# Main_Board.net
KiCad netlist of a schematic drawn in EAGLE
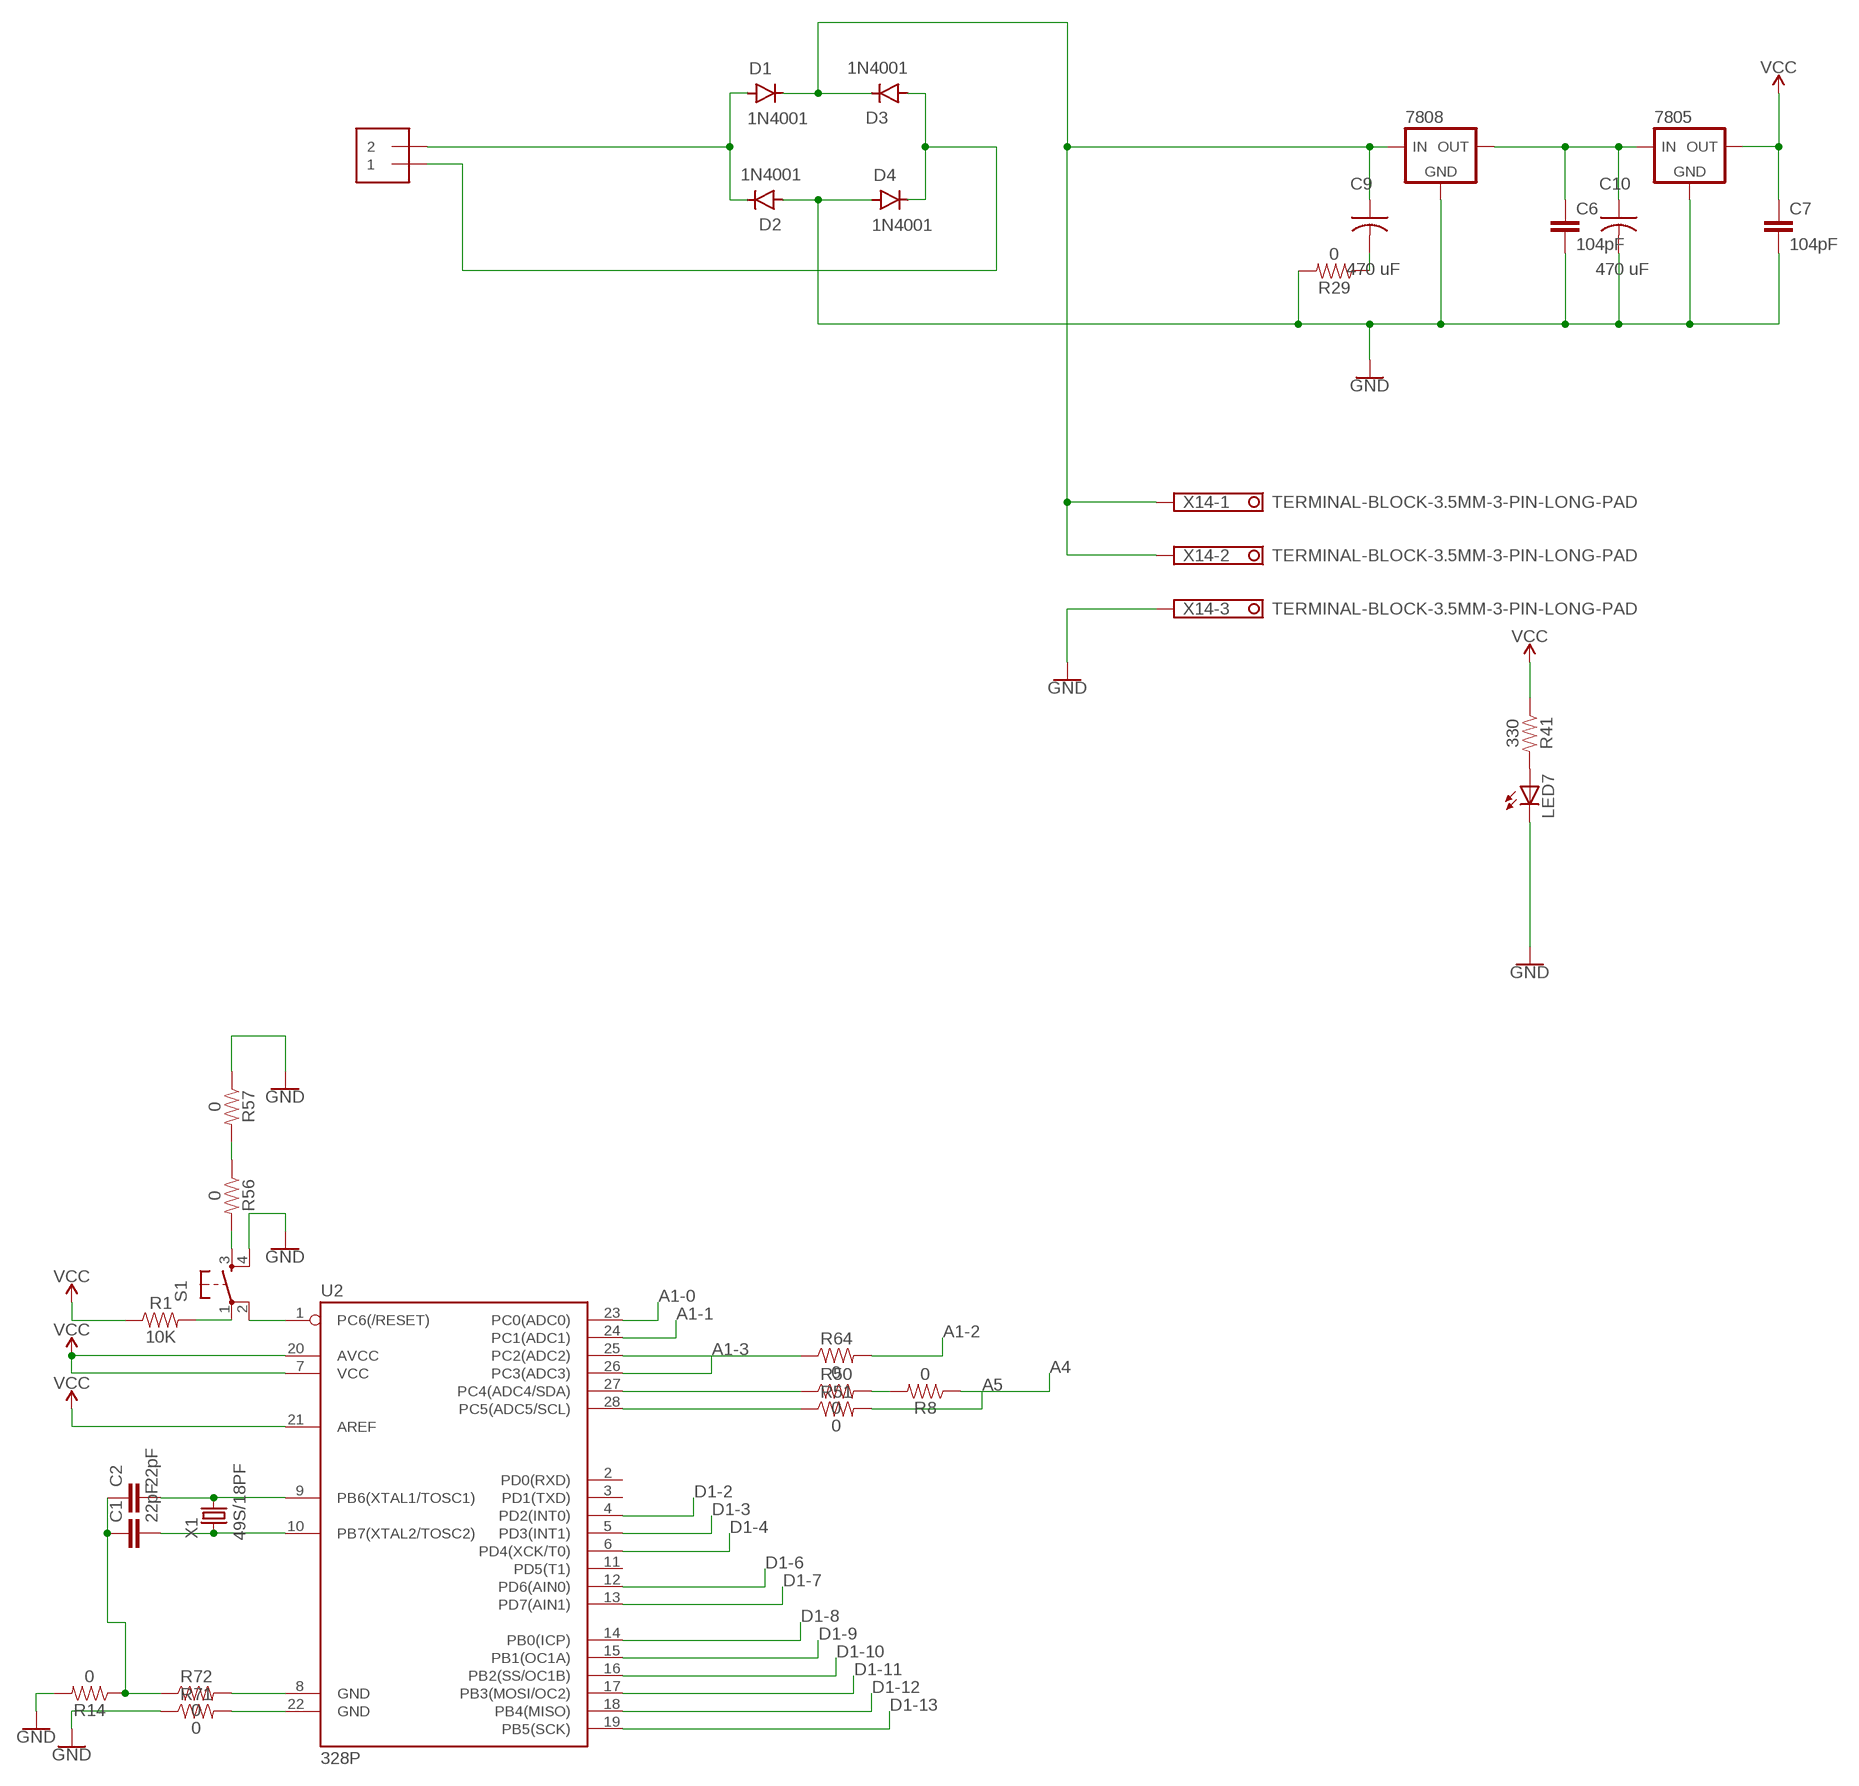
[diagram p0: schematic, sheet 1, part 1 of 3]
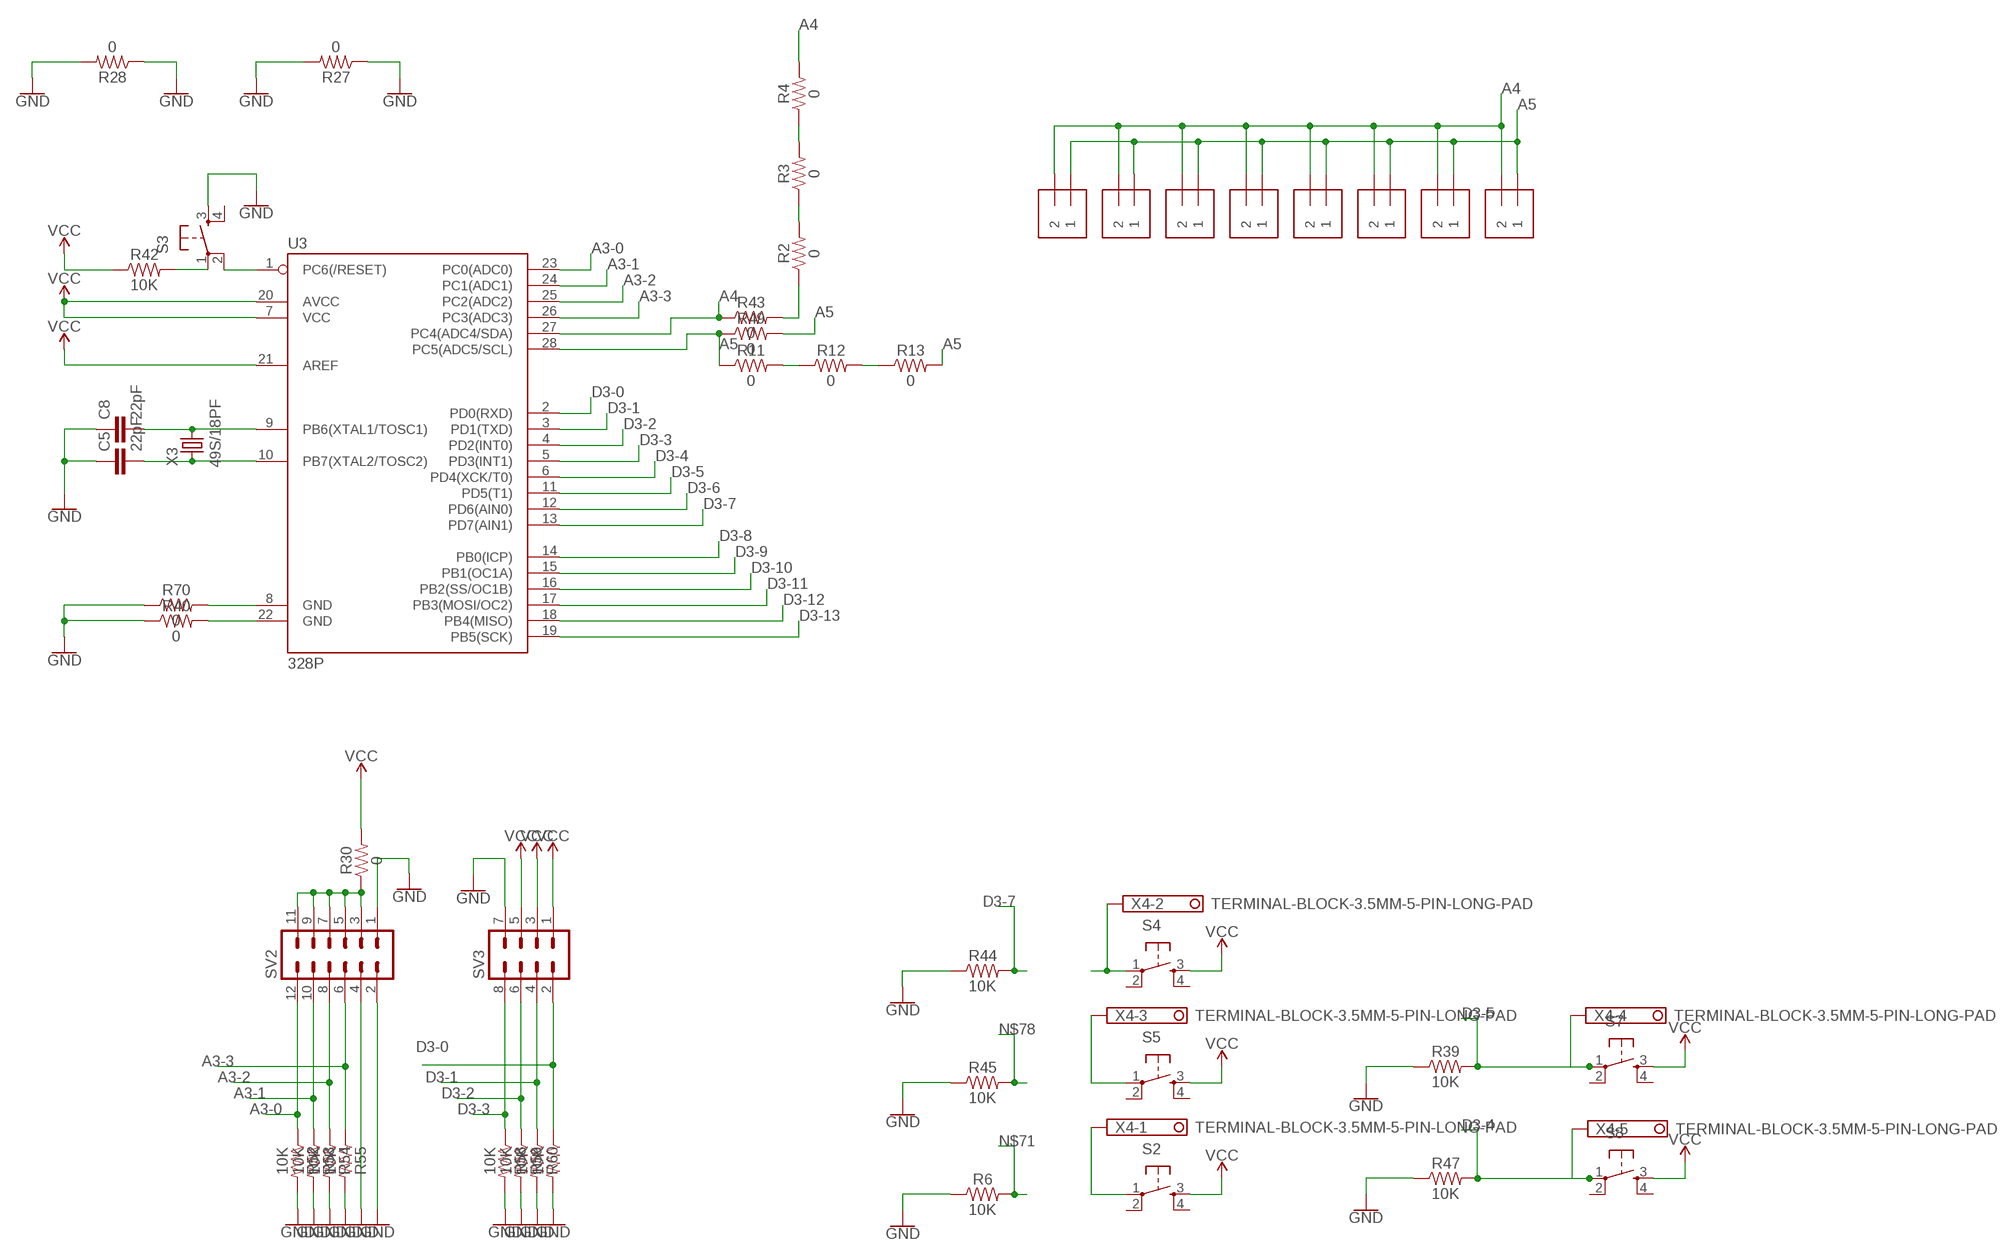
[diagram p1: schematic, sheet 1, part 2 of 3]
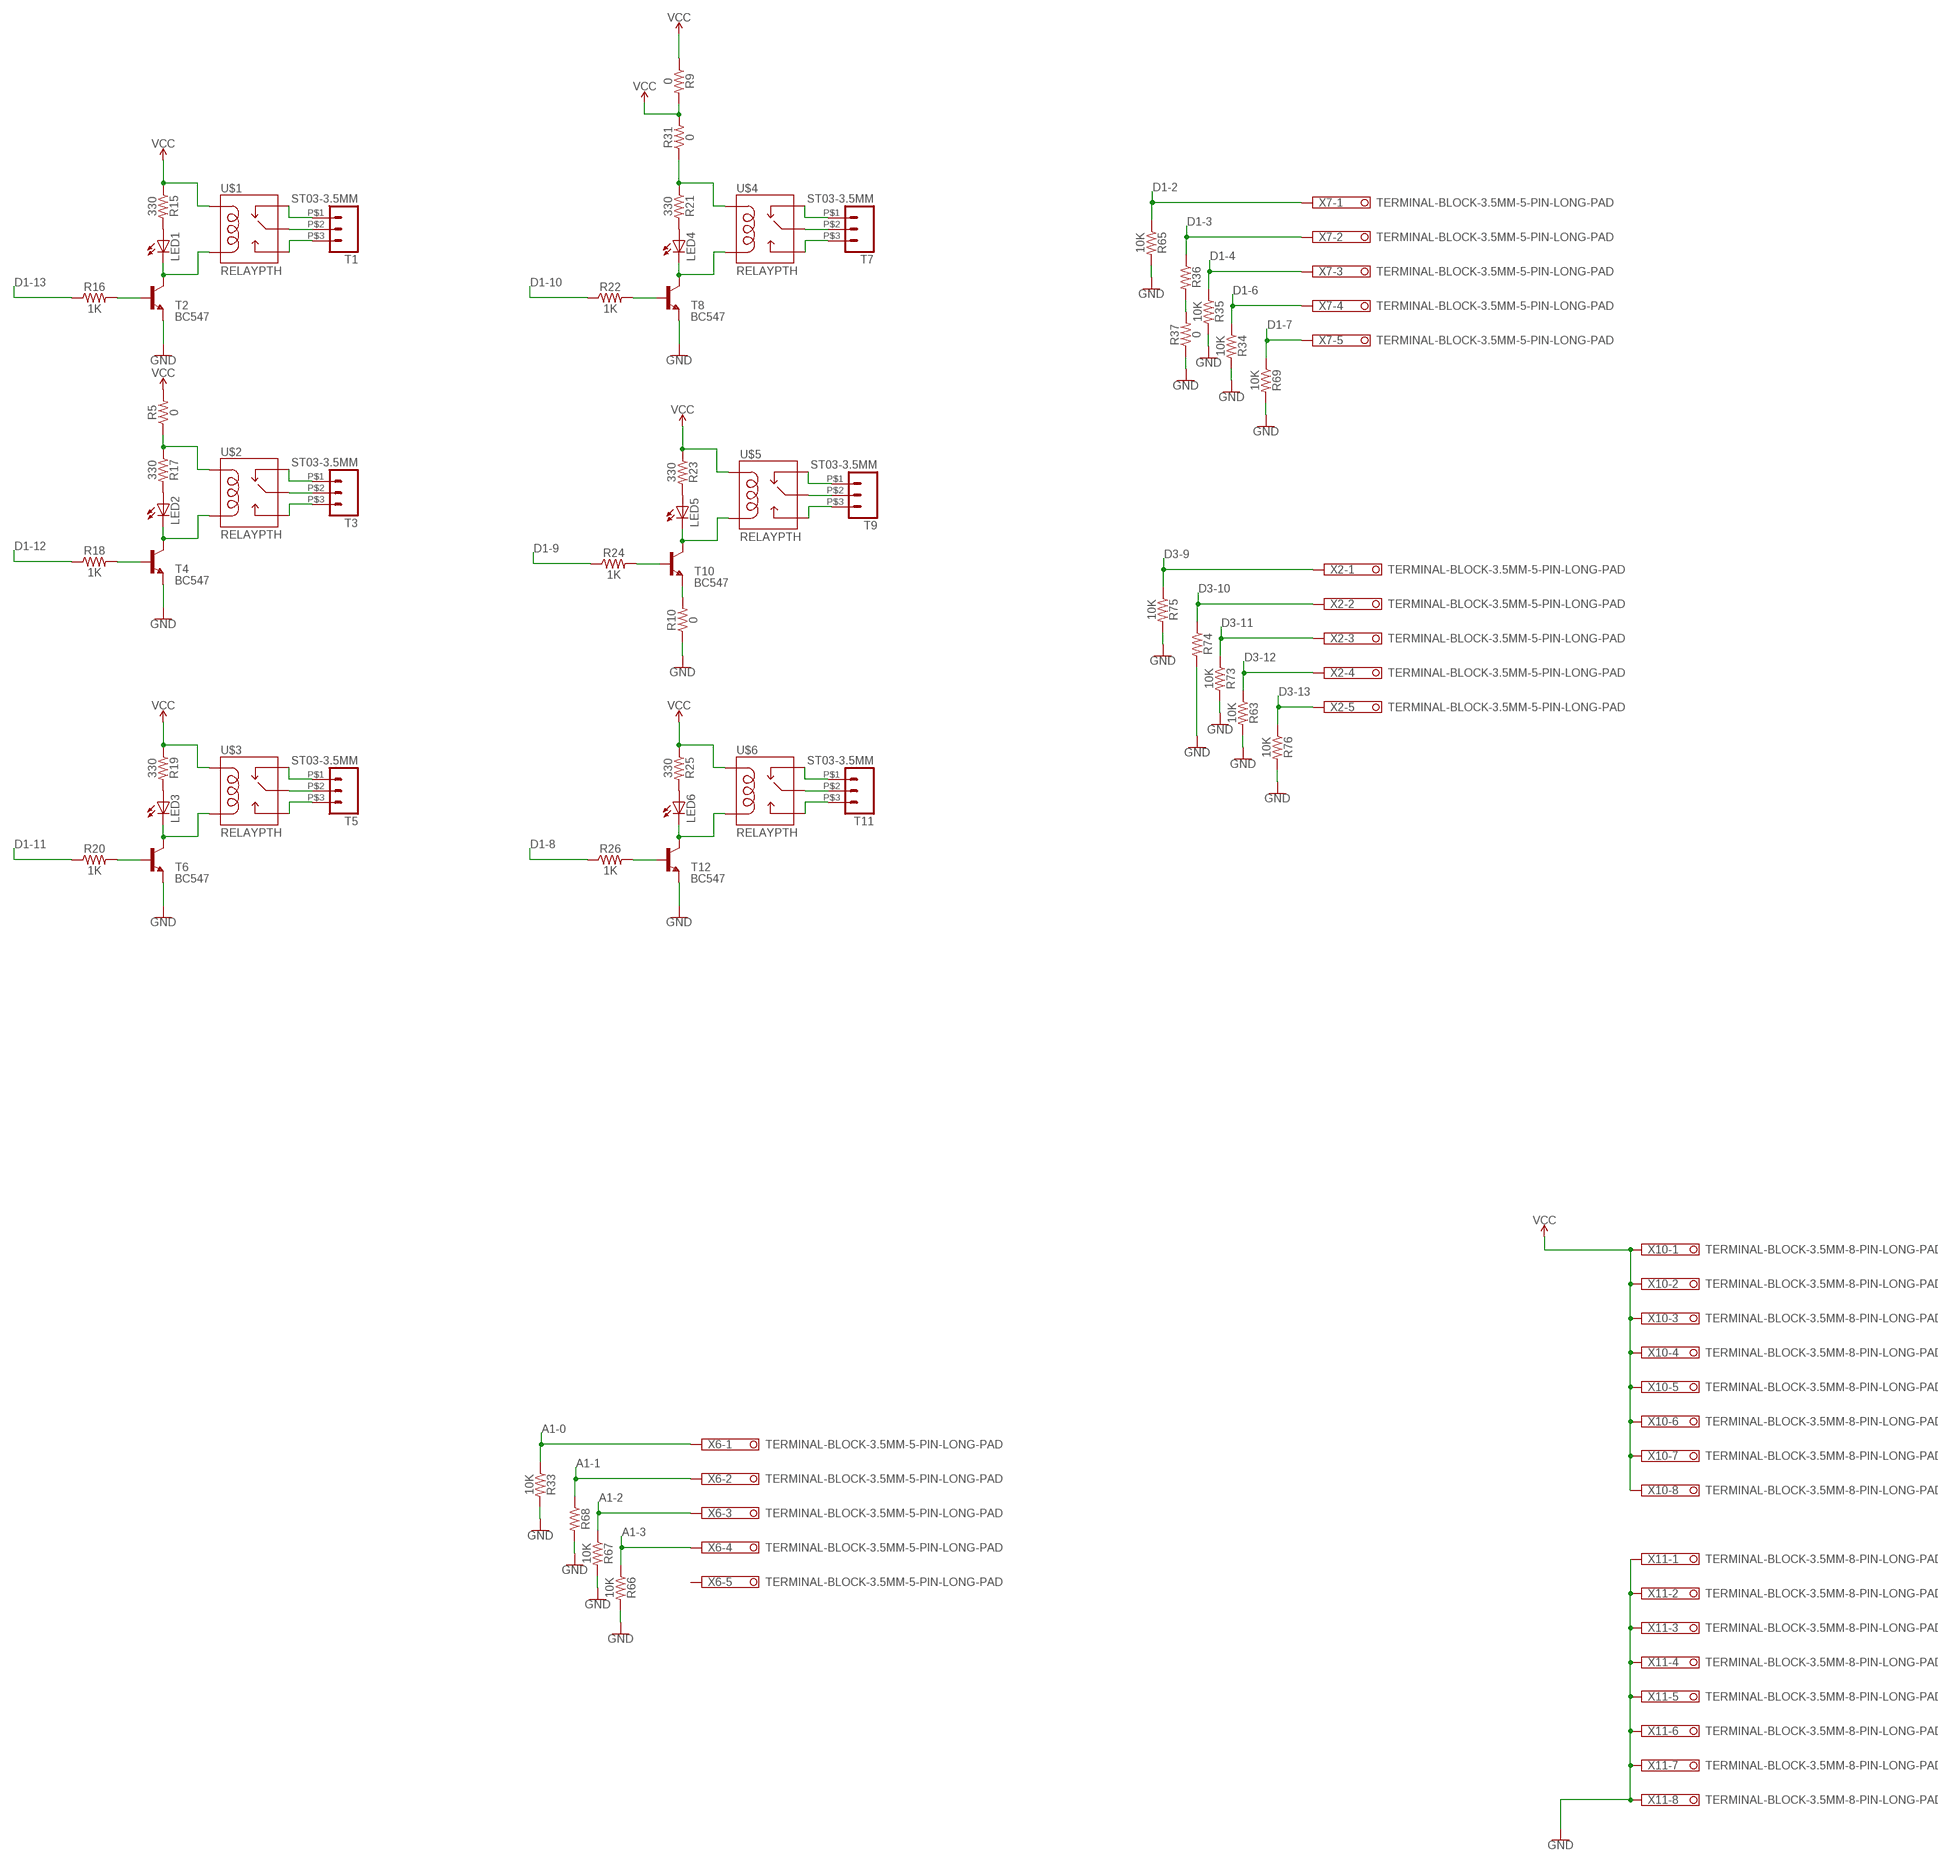
[diagram p2: schematic, sheet 1, part 3 of 3]

(export (version "E")
  (design (tool "Eeschema 10.0.6"))
  (components
    (comp (ref "7805")
      (value "78XX-TO220H-NH")
      (footprint "eagle-import:TO220BH-NH")
      (libsource (lib "eagle-import") (part "78XX-TO220H-NH"))
    )
    (comp (ref "7808")
      (value "78XX-TO220H-NH")
      (footprint "eagle-import:TO220BH-NH")
      (libsource (lib "eagle-import") (part "78XX-TO220H-NH"))
    )
    (comp (ref "C1")
      (value "22pF")
      (footprint "eagle-import:CAP-PTH-2.54")
      (libsource (lib "eagle-import") (part "22PF-PTH-2.54MM-200V-5%"))
    )
    (comp (ref "C2")
      (value "22pF")
      (footprint "eagle-import:CAP-PTH-2.54")
      (libsource (lib "eagle-import") (part "22PF-PTH-2.54MM-200V-5%"))
    )
    (comp (ref "C5")
      (value "22pF")
      (footprint "eagle-import:CAP-PTH-2.54")
      (libsource (lib "eagle-import") (part "22PF-PTH-2.54MM-200V-5%"))
    )
    (comp (ref "C6")
      (value "104pF")
      (footprint "eagle-import:CAP-PTH-2.54")
      (libsource (lib "eagle-import") (part "22PF-PTH-2.54MM-200V-5%"))
    )
    (comp (ref "C7")
      (value "104pF")
      (footprint "eagle-import:CAP-PTH-2.54")
      (libsource (lib "eagle-import") (part "22PF-PTH-2.54MM-200V-5%"))
    )
    (comp (ref "C8")
      (value "22pF")
      (footprint "eagle-import:CAP-PTH-2.54")
      (libsource (lib "eagle-import") (part "22PF-PTH-2.54MM-200V-5%"))
    )
    (comp (ref "C9")
      (value "470 uF")
      (footprint "eagle-import:CAP_RADIAL_5MM")
      (fields
        (field (name "DIGIKEY_PART_NUMBER") "P5156-ND")
        (field (name "MANUFACTURER") "Panasonic Electronic Components")
        (field (name "MPN") "ECA-1EM102")
        (field (name "CREATED_BY") "PCBLayout.com")
      )
      (libsource (lib "eagle-import") (part "ECA-1EM102"))
    )
    (comp (ref "C10")
      (value "470 uF")
      (footprint "eagle-import:CAP_RADIAL_5MM")
      (fields
        (field (name "DIGIKEY_PART_NUMBER") "P5156-ND")
        (field (name "MANUFACTURER") "Panasonic Electronic Components")
        (field (name "MPN") "ECA-1EM102")
        (field (name "CREATED_BY") "PCBLayout.com")
      )
      (libsource (lib "eagle-import") (part "ECA-1EM102"))
    )
    (comp (ref "D1")
      (value "1N4001")
      (footprint "eagle-import:DO-41")
      (fields
        (field (name "DIGIKEY_PART_NUMBER") "1N4004MSCT-ND")
        (field (name "MANUFACTURER") "Micro Commercial Co")
        (field (name "MPN") "1N4004")
        (field (name "CREATED_BY") "PCBLayout.com")
      )
      (libsource (lib "eagle-import") (part "1N4004"))
    )
    (comp (ref "D2")
      (value "1N4001")
      (footprint "eagle-import:DO-41")
      (fields
        (field (name "DIGIKEY_PART_NUMBER") "1N4004MSCT-ND")
        (field (name "MANUFACTURER") "Micro Commercial Co")
        (field (name "MPN") "1N4004")
        (field (name "CREATED_BY") "PCBLayout.com")
      )
      (libsource (lib "eagle-import") (part "1N4004"))
    )
    (comp (ref "D3")
      (value "1N4001")
      (footprint "eagle-import:DO-41")
      (fields
        (field (name "DIGIKEY_PART_NUMBER") "1N4004MSCT-ND")
        (field (name "MANUFACTURER") "Micro Commercial Co")
        (field (name "MPN") "1N4004")
        (field (name "CREATED_BY") "PCBLayout.com")
      )
      (libsource (lib "eagle-import") (part "1N4004"))
    )
    (comp (ref "D4")
      (value "1N4001")
      (footprint "eagle-import:DO-41")
      (fields
        (field (name "DIGIKEY_PART_NUMBER") "1N4004MSCT-ND")
        (field (name "MANUFACTURER") "Micro Commercial Co")
        (field (name "MPN") "1N4004")
        (field (name "CREATED_BY") "PCBLayout.com")
      )
      (libsource (lib "eagle-import") (part "1N4004"))
    )
    (comp (ref "LED1")
      (value "LED5MM")
      (footprint "eagle-import:LED5MM")
      (libsource (lib "eagle-import") (part "LED5MM"))
    )
    (comp (ref "LED2")
      (value "LED5MM")
      (footprint "eagle-import:LED5MM")
      (libsource (lib "eagle-import") (part "LED5MM"))
    )
    (comp (ref "LED3")
      (value "LED5MM")
      (footprint "eagle-import:LED5MM")
      (libsource (lib "eagle-import") (part "LED5MM"))
    )
    (comp (ref "LED4")
      (value "LED5MM")
      (footprint "eagle-import:LED5MM")
      (libsource (lib "eagle-import") (part "LED5MM"))
    )
    (comp (ref "LED5")
      (value "LED5MM")
      (footprint "eagle-import:LED5MM")
      (libsource (lib "eagle-import") (part "LED5MM"))
    )
    (comp (ref "LED6")
      (value "LED5MM")
      (footprint "eagle-import:LED5MM")
      (libsource (lib "eagle-import") (part "LED5MM"))
    )
    (comp (ref "LED7")
      (value "LED5MM")
      (footprint "eagle-import:LED5MM")
      (libsource (lib "eagle-import") (part "LED5MM"))
    )
    (comp (ref "POWER-INPUT")
      (value "1X2-3.5MM")
      (footprint "eagle-import:1X2-3.5MM")
      (libsource (lib "eagle-import") (part "1X2-3.5MM"))
    )
    (comp (ref "POWER-INPUT1")
      (value "1X2-3.5MM")
      (footprint "eagle-import:1X2-3.5MM")
      (libsource (lib "eagle-import") (part "1X2-3.5MM"))
    )
    (comp (ref "POWER-INPUT2")
      (value "1X2-3.5MM")
      (footprint "eagle-import:1X2-3.5MM")
      (libsource (lib "eagle-import") (part "1X2-3.5MM"))
    )
    (comp (ref "POWER-INPUT3")
      (value "1X2-3.5MM")
      (footprint "eagle-import:1X2-3.5MM")
      (libsource (lib "eagle-import") (part "1X2-3.5MM"))
    )
    (comp (ref "POWER-INPUT4")
      (value "1X2-3.5MM")
      (footprint "eagle-import:1X2-3.5MM")
      (libsource (lib "eagle-import") (part "1X2-3.5MM"))
    )
    (comp (ref "POWER-INPUT5")
      (value "1X2-3.5MM")
      (footprint "eagle-import:1X2-3.5MM")
      (libsource (lib "eagle-import") (part "1X2-3.5MM"))
    )
    (comp (ref "POWER-INPUT6")
      (value "1X2-3.5MM")
      (footprint "eagle-import:1X2-3.5MM")
      (libsource (lib "eagle-import") (part "1X2-3.5MM"))
    )
    (comp (ref "POWER-INPUT7")
      (value "1X2-3.5MM")
      (footprint "eagle-import:1X2-3.5MM")
      (libsource (lib "eagle-import") (part "1X2-3.5MM"))
    )
    (comp (ref "POWER-INPUT8")
      (value "1X2-3.5MM")
      (footprint "eagle-import:1X2-3.5MM")
      (libsource (lib "eagle-import") (part "1X2-3.5MM"))
    )
    (comp (ref "R1")
      (value "10K")
      (footprint "eagle-import:AXIAL-0.3")
      (libsource (lib "eagle-import") (part "10MOHM-HORIZ-1/4W-5%"))
    )
    (comp (ref "R2")
      (value "0")
      (footprint "eagle-import:AXIAL-0.3")
      (libsource (lib "eagle-import") (part "10MOHM-HORIZ-1/4W-5%"))
    )
    (comp (ref "R3")
      (value "0")
      (footprint "eagle-import:AXIAL-0.3")
      (libsource (lib "eagle-import") (part "10MOHM-HORIZ-1/4W-5%"))
    )
    (comp (ref "R4")
      (value "0")
      (footprint "eagle-import:AXIAL-0.3")
      (libsource (lib "eagle-import") (part "10MOHM-HORIZ-1/4W-5%"))
    )
    (comp (ref "R5")
      (value "0")
      (footprint "eagle-import:AXIAL-0.3")
      (libsource (lib "eagle-import") (part "10MOHM-HORIZ-1/4W-5%"))
    )
    (comp (ref "R6")
      (value "10K")
      (footprint "eagle-import:AXIAL-0.3")
      (libsource (lib "eagle-import") (part "10MOHM-HORIZ-1/4W-5%"))
    )
    (comp (ref "R8")
      (value "0")
      (footprint "eagle-import:AXIAL-0.3")
      (libsource (lib "eagle-import") (part "10MOHM-HORIZ-1/4W-5%"))
    )
    (comp (ref "R9")
      (value "0")
      (footprint "eagle-import:AXIAL-0.3")
      (libsource (lib "eagle-import") (part "10MOHM-HORIZ-1/4W-5%"))
    )
    (comp (ref "R10")
      (value "0")
      (footprint "eagle-import:AXIAL-0.3")
      (libsource (lib "eagle-import") (part "10MOHM-HORIZ-1/4W-5%"))
    )
    (comp (ref "R11")
      (value "0")
      (footprint "eagle-import:AXIAL-0.3")
      (libsource (lib "eagle-import") (part "10MOHM-HORIZ-1/4W-5%"))
    )
    (comp (ref "R12")
      (value "0")
      (footprint "eagle-import:AXIAL-0.3")
      (libsource (lib "eagle-import") (part "10MOHM-HORIZ-1/4W-5%"))
    )
    (comp (ref "R13")
      (value "0")
      (footprint "eagle-import:AXIAL-0.3")
      (libsource (lib "eagle-import") (part "10MOHM-HORIZ-1/4W-5%"))
    )
    (comp (ref "R14")
      (value "0")
      (footprint "eagle-import:AXIAL-0.3")
      (libsource (lib "eagle-import") (part "10MOHM-HORIZ-1/4W-5%"))
    )
    (comp (ref "R15")
      (value "330")
      (footprint "eagle-import:AXIAL-0.3")
      (libsource (lib "eagle-import") (part "10MOHM-HORIZ-1/4W-5%"))
    )
    (comp (ref "R16")
      (value "1K")
      (footprint "eagle-import:AXIAL-0.3")
      (libsource (lib "eagle-import") (part "10MOHM-HORIZ-1/4W-5%"))
    )
    (comp (ref "R17")
      (value "330")
      (footprint "eagle-import:AXIAL-0.3")
      (libsource (lib "eagle-import") (part "10MOHM-HORIZ-1/4W-5%"))
    )
    (comp (ref "R18")
      (value "1K")
      (footprint "eagle-import:AXIAL-0.3")
      (libsource (lib "eagle-import") (part "10MOHM-HORIZ-1/4W-5%"))
    )
    (comp (ref "R19")
      (value "330")
      (footprint "eagle-import:AXIAL-0.3")
      (libsource (lib "eagle-import") (part "10MOHM-HORIZ-1/4W-5%"))
    )
    (comp (ref "R20")
      (value "1K")
      (footprint "eagle-import:AXIAL-0.3")
      (libsource (lib "eagle-import") (part "10MOHM-HORIZ-1/4W-5%"))
    )
    (comp (ref "R21")
      (value "330")
      (footprint "eagle-import:AXIAL-0.3")
      (libsource (lib "eagle-import") (part "10MOHM-HORIZ-1/4W-5%"))
    )
    (comp (ref "R22")
      (value "1K")
      (footprint "eagle-import:AXIAL-0.3")
      (libsource (lib "eagle-import") (part "10MOHM-HORIZ-1/4W-5%"))
    )
    (comp (ref "R23")
      (value "330")
      (footprint "eagle-import:AXIAL-0.3")
      (libsource (lib "eagle-import") (part "10MOHM-HORIZ-1/4W-5%"))
    )
    (comp (ref "R24")
      (value "1K")
      (footprint "eagle-import:AXIAL-0.3")
      (libsource (lib "eagle-import") (part "10MOHM-HORIZ-1/4W-5%"))
    )
    (comp (ref "R25")
      (value "330")
      (footprint "eagle-import:AXIAL-0.3")
      (libsource (lib "eagle-import") (part "10MOHM-HORIZ-1/4W-5%"))
    )
    (comp (ref "R26")
      (value "1K")
      (footprint "eagle-import:AXIAL-0.3")
      (libsource (lib "eagle-import") (part "10MOHM-HORIZ-1/4W-5%"))
    )
    (comp (ref "R27")
      (value "0")
      (footprint "eagle-import:AXIAL-0.3")
      (libsource (lib "eagle-import") (part "10MOHM-HORIZ-1/4W-5%"))
    )
    (comp (ref "R28")
      (value "0")
      (footprint "eagle-import:AXIAL-0.3")
      (libsource (lib "eagle-import") (part "10MOHM-HORIZ-1/4W-5%"))
    )
    (comp (ref "R29")
      (value "0")
      (footprint "eagle-import:AXIAL-0.3")
      (libsource (lib "eagle-import") (part "10MOHM-HORIZ-1/4W-5%"))
    )
    (comp (ref "R30")
      (value "0")
      (footprint "eagle-import:AXIAL-0.3")
      (libsource (lib "eagle-import") (part "10MOHM-HORIZ-1/4W-5%"))
    )
    (comp (ref "R31")
      (value "0")
      (footprint "eagle-import:AXIAL-0.3")
      (libsource (lib "eagle-import") (part "10MOHM-HORIZ-1/4W-5%"))
    )
    (comp (ref "R33")
      (value "10K")
      (footprint "eagle-import:AXIAL-0.3")
      (libsource (lib "eagle-import") (part "10MOHM-HORIZ-1/4W-5%"))
    )
    (comp (ref "R34")
      (value "10K")
      (footprint "eagle-import:AXIAL-0.3")
      (libsource (lib "eagle-import") (part "10MOHM-HORIZ-1/4W-5%"))
    )
    (comp (ref "R35")
      (value "10K")
      (footprint "eagle-import:AXIAL-0.3")
      (libsource (lib "eagle-import") (part "10MOHM-HORIZ-1/4W-5%"))
    )
    (comp (ref "R36")
      (value "10K")
      (footprint "eagle-import:AXIAL-0.3")
      (libsource (lib "eagle-import") (part "10MOHM-HORIZ-1/4W-5%"))
    )
    (comp (ref "R37")
      (value "0")
      (footprint "eagle-import:AXIAL-0.3")
      (libsource (lib "eagle-import") (part "10MOHM-HORIZ-1/4W-5%"))
    )
    (comp (ref "R39")
      (value "10K")
      (footprint "eagle-import:AXIAL-0.3")
      (libsource (lib "eagle-import") (part "10MOHM-HORIZ-1/4W-5%"))
    )
    (comp (ref "R40")
      (value "0")
      (footprint "eagle-import:AXIAL-0.3")
      (libsource (lib "eagle-import") (part "10MOHM-HORIZ-1/4W-5%"))
    )
    (comp (ref "R41")
      (value "330")
      (footprint "eagle-import:AXIAL-0.3")
      (libsource (lib "eagle-import") (part "10MOHM-HORIZ-1/4W-5%"))
    )
    (comp (ref "R42")
      (value "10K")
      (footprint "eagle-import:AXIAL-0.3")
      (libsource (lib "eagle-import") (part "10MOHM-HORIZ-1/4W-5%"))
    )
    (comp (ref "R43")
      (value "0")
      (footprint "eagle-import:AXIAL-0.3")
      (libsource (lib "eagle-import") (part "10MOHM-HORIZ-1/4W-5%"))
    )
    (comp (ref "R44")
      (value "10K")
      (footprint "eagle-import:AXIAL-0.3")
      (libsource (lib "eagle-import") (part "10MOHM-HORIZ-1/4W-5%"))
    )
    (comp (ref "R45")
      (value "10K")
      (footprint "eagle-import:AXIAL-0.3")
      (libsource (lib "eagle-import") (part "10MOHM-HORIZ-1/4W-5%"))
    )
    (comp (ref "R47")
      (value "10K")
      (footprint "eagle-import:AXIAL-0.3")
      (libsource (lib "eagle-import") (part "10MOHM-HORIZ-1/4W-5%"))
    )
    (comp (ref "R49")
      (value "0")
      (footprint "eagle-import:AXIAL-0.3")
      (libsource (lib "eagle-import") (part "10MOHM-HORIZ-1/4W-5%"))
    )
    (comp (ref "R50")
      (value "0")
      (footprint "eagle-import:AXIAL-0.3")
      (libsource (lib "eagle-import") (part "10MOHM-HORIZ-1/4W-5%"))
    )
    (comp (ref "R51")
      (value "0")
      (footprint "eagle-import:AXIAL-0.3")
      (libsource (lib "eagle-import") (part "10MOHM-HORIZ-1/4W-5%"))
    )
    (comp (ref "R52")
      (value "10K")
      (footprint "eagle-import:AXIAL-0.3")
      (libsource (lib "eagle-import") (part "10MOHM-HORIZ-1/4W-5%"))
    )
    (comp (ref "R53")
      (value "10K")
      (footprint "eagle-import:AXIAL-0.3")
      (libsource (lib "eagle-import") (part "10MOHM-HORIZ-1/4W-5%"))
    )
    (comp (ref "R54")
      (value "10K")
      (footprint "eagle-import:AXIAL-0.3")
      (libsource (lib "eagle-import") (part "10MOHM-HORIZ-1/4W-5%"))
    )
    (comp (ref "R55")
      (value "10K")
      (footprint "eagle-import:AXIAL-0.3")
      (libsource (lib "eagle-import") (part "10MOHM-HORIZ-1/4W-5%"))
    )
    (comp (ref "R56")
      (value "0")
      (footprint "eagle-import:AXIAL-0.3")
      (libsource (lib "eagle-import") (part "10MOHM-HORIZ-1/4W-5%"))
    )
    (comp (ref "R57")
      (value "0")
      (footprint "eagle-import:AXIAL-0.3")
      (libsource (lib "eagle-import") (part "10MOHM-HORIZ-1/4W-5%"))
    )
    (comp (ref "R58")
      (value "10K")
      (footprint "eagle-import:AXIAL-0.3")
      (libsource (lib "eagle-import") (part "10MOHM-HORIZ-1/4W-5%"))
    )
    (comp (ref "R59")
      (value "10K")
      (footprint "eagle-import:AXIAL-0.3")
      (libsource (lib "eagle-import") (part "10MOHM-HORIZ-1/4W-5%"))
    )
    (comp (ref "R60")
      (value "10K")
      (footprint "eagle-import:AXIAL-0.3")
      (libsource (lib "eagle-import") (part "10MOHM-HORIZ-1/4W-5%"))
    )
    (comp (ref "R61")
      (value "10K")
      (footprint "eagle-import:AXIAL-0.3")
      (libsource (lib "eagle-import") (part "10MOHM-HORIZ-1/4W-5%"))
    )
    (comp (ref "R63")
      (value "10K")
      (footprint "eagle-import:AXIAL-0.3")
      (libsource (lib "eagle-import") (part "10MOHM-HORIZ-1/4W-5%"))
    )
    (comp (ref "R64")
      (value "0")
      (footprint "eagle-import:AXIAL-0.3")
      (libsource (lib "eagle-import") (part "10MOHM-HORIZ-1/4W-5%"))
    )
    (comp (ref "R65")
      (value "10K")
      (footprint "eagle-import:AXIAL-0.3")
      (libsource (lib "eagle-import") (part "10MOHM-HORIZ-1/4W-5%"))
    )
    (comp (ref "R66")
      (value "10K")
      (footprint "eagle-import:AXIAL-0.3")
      (libsource (lib "eagle-import") (part "10MOHM-HORIZ-1/4W-5%"))
    )
    (comp (ref "R67")
      (value "10K")
      (footprint "eagle-import:AXIAL-0.3")
      (libsource (lib "eagle-import") (part "10MOHM-HORIZ-1/4W-5%"))
    )
    (comp (ref "R68")
      (value "10K")
      (footprint "eagle-import:AXIAL-0.3")
      (libsource (lib "eagle-import") (part "10MOHM-HORIZ-1/4W-5%"))
    )
    (comp (ref "R69")
      (value "10K")
      (footprint "eagle-import:AXIAL-0.3")
      (libsource (lib "eagle-import") (part "10MOHM-HORIZ-1/4W-5%"))
    )
    (comp (ref "R70")
      (value "0")
      (footprint "eagle-import:AXIAL-0.3")
      (libsource (lib "eagle-import") (part "10MOHM-HORIZ-1/4W-5%"))
    )
    (comp (ref "R71")
      (value "0")
      (footprint "eagle-import:AXIAL-0.3")
      (libsource (lib "eagle-import") (part "10MOHM-HORIZ-1/4W-5%"))
    )
    (comp (ref "R72")
      (value "0")
      (footprint "eagle-import:AXIAL-0.3")
      (libsource (lib "eagle-import") (part "10MOHM-HORIZ-1/4W-5%"))
    )
    (comp (ref "R73")
      (value "10K")
      (footprint "eagle-import:AXIAL-0.3")
      (libsource (lib "eagle-import") (part "10MOHM-HORIZ-1/4W-5%"))
    )
    (comp (ref "R74")
      (value "10K")
      (footprint "eagle-import:AXIAL-0.3")
      (libsource (lib "eagle-import") (part "10MOHM-HORIZ-1/4W-5%"))
    )
    (comp (ref "R75")
      (value "10K")
      (footprint "eagle-import:AXIAL-0.3")
      (libsource (lib "eagle-import") (part "10MOHM-HORIZ-1/4W-5%"))
    )
    (comp (ref "R76")
      (value "10K")
      (footprint "eagle-import:AXIAL-0.3")
      (libsource (lib "eagle-import") (part "10MOHM-HORIZ-1/4W-5%"))
    )
    (comp (ref "S1")
      (value "TAC_SWITCHPTH")
      (footprint "eagle-import:TACTILE-PTH")
      (libsource (lib "eagle-import") (part "TAC_SWITCHPTH"))
    )
    (comp (ref "S2")
      (value "TAC_SWITCHPTH")
      (footprint "eagle-import:TACTILE-PTH")
      (libsource (lib "eagle-import") (part "TAC_SWITCHPTH"))
    )
    (comp (ref "S3")
      (value "TAC_SWITCHPTH")
      (footprint "eagle-import:TACTILE-PTH")
      (libsource (lib "eagle-import") (part "TAC_SWITCHPTH"))
    )
    (comp (ref "S4")
      (value "TAC_SWITCHPTH")
      (footprint "eagle-import:TACTILE-PTH")
      (libsource (lib "eagle-import") (part "TAC_SWITCHPTH"))
    )
    (comp (ref "S5")
      (value "TAC_SWITCHPTH")
      (footprint "eagle-import:TACTILE-PTH")
      (libsource (lib "eagle-import") (part "TAC_SWITCHPTH"))
    )
    (comp (ref "S7")
      (value "TAC_SWITCHPTH")
      (footprint "eagle-import:TACTILE-PTH")
      (libsource (lib "eagle-import") (part "TAC_SWITCHPTH"))
    )
    (comp (ref "S8")
      (value "TAC_SWITCHPTH")
      (footprint "eagle-import:TACTILE-PTH")
      (libsource (lib "eagle-import") (part "TAC_SWITCHPTH"))
    )
    (comp (ref "SV2")
      (value "MA06-2")
      (footprint "eagle-import:MA06-2")
      (libsource (lib "eagle-import") (part "MA06-2"))
    )
    (comp (ref "SV3")
      (value "MA04-2")
      (footprint "eagle-import:MA04-2")
      (libsource (lib "eagle-import") (part "MA04-2"))
    )
    (comp (ref "T1")
      (value "ST03-3.5MM")
      (footprint "eagle-import:ED350V-03P")
      (libsource (lib "eagle-import") (part "ST03-3.5MM"))
    )
    (comp (ref "T2")
      (value "BC547")
      (footprint "eagle-import:TO92")
      (libsource (lib "eagle-import") (part "BC547"))
    )
    (comp (ref "T3")
      (value "ST03-3.5MM")
      (footprint "eagle-import:ED350V-03P")
      (libsource (lib "eagle-import") (part "ST03-3.5MM"))
    )
    (comp (ref "T4")
      (value "BC547")
      (footprint "eagle-import:TO92")
      (libsource (lib "eagle-import") (part "BC547"))
    )
    (comp (ref "T5")
      (value "ST03-3.5MM")
      (footprint "eagle-import:ED350V-03P")
      (libsource (lib "eagle-import") (part "ST03-3.5MM"))
    )
    (comp (ref "T6")
      (value "BC547")
      (footprint "eagle-import:TO92")
      (libsource (lib "eagle-import") (part "BC547"))
    )
    (comp (ref "T7")
      (value "ST03-3.5MM")
      (footprint "eagle-import:ED350V-03P")
      (libsource (lib "eagle-import") (part "ST03-3.5MM"))
    )
    (comp (ref "T8")
      (value "BC547")
      (footprint "eagle-import:TO92")
      (libsource (lib "eagle-import") (part "BC547"))
    )
    (comp (ref "T9")
      (value "ST03-3.5MM")
      (footprint "eagle-import:ED350V-03P")
      (libsource (lib "eagle-import") (part "ST03-3.5MM"))
    )
    (comp (ref "T10")
      (value "BC547")
      (footprint "eagle-import:TO92")
      (libsource (lib "eagle-import") (part "BC547"))
    )
    (comp (ref "T11")
      (value "ST03-3.5MM")
      (footprint "eagle-import:ED350V-03P")
      (libsource (lib "eagle-import") (part "ST03-3.5MM"))
    )
    (comp (ref "T12")
      (value "BC547")
      (footprint "eagle-import:TO92")
      (libsource (lib "eagle-import") (part "BC547"))
    )
    (comp (ref "U$1")
      (value "RELAYPTH")
      (footprint "eagle-import:SRD-05VDC-SL-C")
      (libsource (lib "eagle-import") (part "RELAYPTH"))
    )
    (comp (ref "U$2")
      (value "RELAYPTH")
      (footprint "eagle-import:SRD-05VDC-SL-C")
      (libsource (lib "eagle-import") (part "RELAYPTH"))
    )
    (comp (ref "U$3")
      (value "RELAYPTH")
      (footprint "eagle-import:SRD-05VDC-SL-C")
      (libsource (lib "eagle-import") (part "RELAYPTH"))
    )
    (comp (ref "U$4")
      (value "RELAYPTH")
      (footprint "eagle-import:SRD-05VDC-SL-C")
      (libsource (lib "eagle-import") (part "RELAYPTH"))
    )
    (comp (ref "U$5")
      (value "RELAYPTH")
      (footprint "eagle-import:SRD-05VDC-SL-C")
      (libsource (lib "eagle-import") (part "RELAYPTH"))
    )
    (comp (ref "U$6")
      (value "RELAYPTH")
      (footprint "eagle-import:SRD-05VDC-SL-C")
      (libsource (lib "eagle-import") (part "RELAYPTH"))
    )
    (comp (ref "U2")
      (value "328P")
      (footprint "eagle-import:DIP28")
      (libsource (lib "eagle-import") (part "ATMEGA328P_PDIP"))
    )
    (comp (ref "U3")
      (value "328P")
      (footprint "eagle-import:DIP28")
      (libsource (lib "eagle-import") (part "ATMEGA328P_PDIP"))
    )
    (comp (ref "X1")
      (value "49S/18PF")
      (footprint "eagle-import:XTAL_HC49")
      (fields (field (name "MANUFACTURER") "Xinhunjing ") (field (name "CREATED_BY") "PCBLayout.com"))
      (libsource (lib "eagle-import") (part "49S/18PF"))
    )
    (comp (ref "X2")
      (value "TERMINAL-BLOCK-3.5MM-5-PIN-LONG-PAD")
      (footprint "eagle-import:TERMINAL-BLOCK-5-PIN-3.5MM-LONG-PAD")
      (libsource (lib "eagle-import") (part "TERMINAL-BLOCK-3.5MM-5-PIN-LONG-PAD"))
    )
    (comp (ref "X3")
      (value "49S/18PF")
      (footprint "eagle-import:XTAL_HC49")
      (fields (field (name "MANUFACTURER") "Xinhunjing ") (field (name "CREATED_BY") "PCBLayout.com"))
      (libsource (lib "eagle-import") (part "49S/18PF"))
    )
    (comp (ref "X4")
      (value "TERMINAL-BLOCK-3.5MM-5-PIN-LONG-PAD")
      (footprint "eagle-import:TERMINAL-BLOCK-5-PIN-3.5MM-LONG-PAD")
      (libsource (lib "eagle-import") (part "TERMINAL-BLOCK-3.5MM-5-PIN-LONG-PAD"))
    )
    (comp (ref "X6")
      (value "TERMINAL-BLOCK-3.5MM-5-PIN-LONG-PAD")
      (footprint "eagle-import:TERMINAL-BLOCK-5-PIN-3.5MM-LONG-PAD")
      (libsource (lib "eagle-import") (part "TERMINAL-BLOCK-3.5MM-5-PIN-LONG-PAD"))
    )
    (comp (ref "X7")
      (value "TERMINAL-BLOCK-3.5MM-5-PIN-LONG-PAD")
      (footprint "eagle-import:TERMINAL-BLOCK-5-PIN-3.5MM-LONG-PAD")
      (libsource (lib "eagle-import") (part "TERMINAL-BLOCK-3.5MM-5-PIN-LONG-PAD"))
    )
    (comp (ref "X10")
      (value "TERMINAL-BLOCK-3.5MM-8-PIN-LONG-PAD")
      (footprint "eagle-import:TERMINAL-BLOCK-8-PIN-3.5MM-LONG-PAD")
      (libsource (lib "eagle-import") (part "TERMINAL-BLOCK-3.5MM-8-PIN-LONG-PAD"))
    )
    (comp (ref "X11")
      (value "TERMINAL-BLOCK-3.5MM-8-PIN-LONG-PAD")
      (footprint "eagle-import:TERMINAL-BLOCK-8-PIN-3.5MM-LONG-PAD")
      (libsource (lib "eagle-import") (part "TERMINAL-BLOCK-3.5MM-8-PIN-LONG-PAD"))
    )
    (comp (ref "X14")
      (value "TERMINAL-BLOCK-3.5MM-3-PIN-LONG-PAD")
      (footprint "eagle-import:TERMINAL-BLOCK-3-PIN-3.5MM-LONG-PAD")
      (libsource (lib "eagle-import") (part "TERMINAL-BLOCK-3.5MM-3-PIN-LONG-PAD"))
    )
  )
  (nets
    (net (code "1") (name "/A1-0") (class "Default")
      (node (ref "R33") (pin "P$1") (pinfunction "1_P$1") (pintype "passive"))
      (node (ref "U2") (pin "23") (pinfunction "PC0(ADC0)_23") (pintype "bidirectional"))
      (node (ref "X6") (pin "1") (pinfunction "K_1") (pintype "passive"))
    )
    (net (code "2") (name "/A1-1") (class "Default")
      (node (ref "R68") (pin "P$1") (pinfunction "1_P$1") (pintype "passive"))
      (node (ref "U2") (pin "24") (pinfunction "PC1(ADC1)_24") (pintype "bidirectional"))
      (node (ref "X6") (pin "2") (pinfunction "K_2") (pintype "passive"))
    )
    (net (code "3") (name "/A1-2") (class "Default")
      (node (ref "R64") (pin "P$2") (pinfunction "2_P$2") (pintype "passive"))
      (node (ref "R67") (pin "P$1") (pinfunction "1_P$1") (pintype "passive"))
      (node (ref "X6") (pin "3") (pinfunction "K_3") (pintype "passive"))
    )
    (net (code "4") (name "/A1-3") (class "Default")
      (node (ref "R66") (pin "P$1") (pinfunction "1_P$1") (pintype "passive"))
      (node (ref "U2") (pin "26") (pinfunction "PC3(ADC3)_26") (pintype "bidirectional"))
      (node (ref "X6") (pin "4") (pinfunction "K_4") (pintype "passive"))
    )
    (net (code "5") (name "/A3-0") (class "Default")
      (node (ref "R52") (pin "P$1") (pinfunction "1_P$1") (pintype "passive"))
      (node (ref "SV2") (pin "12") (pinfunction "12_12") (pintype "passive"))
      (node (ref "U3") (pin "23") (pinfunction "PC0(ADC0)_23") (pintype "bidirectional"))
    )
    (net (code "6") (name "/A3-1") (class "Default")
      (node (ref "R53") (pin "P$1") (pinfunction "1_P$1") (pintype "passive"))
      (node (ref "SV2") (pin "10") (pinfunction "10_10") (pintype "passive"))
      (node (ref "U3") (pin "24") (pinfunction "PC1(ADC1)_24") (pintype "bidirectional"))
    )
    (net (code "7") (name "/A3-2") (class "Default")
      (node (ref "R54") (pin "P$1") (pinfunction "1_P$1") (pintype "passive"))
      (node (ref "SV2") (pin "8") (pinfunction "8_8") (pintype "passive"))
      (node (ref "U3") (pin "25") (pinfunction "PC2(ADC2)_25") (pintype "bidirectional"))
    )
    (net (code "8") (name "/A3-3") (class "Default")
      (node (ref "R55") (pin "P$1") (pinfunction "1_P$1") (pintype "passive"))
      (node (ref "SV2") (pin "6") (pinfunction "6_6") (pintype "passive"))
      (node (ref "U3") (pin "26") (pinfunction "PC3(ADC3)_26") (pintype "bidirectional"))
    )
    (net (code "9") (name "/A4") (class "Default")
      (node (ref "POWER-INPUT1") (pin "2") (pinfunction "2_2") (pintype "passive"))
      (node (ref "POWER-INPUT2") (pin "2") (pinfunction "2_2") (pintype "passive"))
      (node (ref "POWER-INPUT3") (pin "2") (pinfunction "2_2") (pintype "passive"))
      (node (ref "POWER-INPUT4") (pin "2") (pinfunction "2_2") (pintype "passive"))
      (node (ref "POWER-INPUT5") (pin "2") (pinfunction "2_2") (pintype "passive"))
      (node (ref "POWER-INPUT6") (pin "2") (pinfunction "2_2") (pintype "passive"))
      (node (ref "POWER-INPUT7") (pin "2") (pinfunction "2_2") (pintype "passive"))
      (node (ref "POWER-INPUT8") (pin "2") (pinfunction "2_2") (pintype "passive"))
      (node (ref "R4") (pin "P$2") (pinfunction "2_P$2") (pintype "passive"))
      (node (ref "R43") (pin "P$1") (pinfunction "1_P$1") (pintype "passive"))
      (node (ref "R8") (pin "P$1") (pinfunction "1_P$1") (pintype "passive"))
      (node (ref "U3") (pin "27") (pinfunction "PC4(ADC4/SDA)_27") (pintype "bidirectional"))
    )
    (net (code "10") (name "/A5") (class "Default")
      (node (ref "POWER-INPUT1") (pin "1") (pinfunction "1_1") (pintype "passive"))
      (node (ref "POWER-INPUT2") (pin "1") (pinfunction "1_1") (pintype "passive"))
      (node (ref "POWER-INPUT3") (pin "1") (pinfunction "1_1") (pintype "passive"))
      (node (ref "POWER-INPUT4") (pin "1") (pinfunction "1_1") (pintype "passive"))
      (node (ref "POWER-INPUT5") (pin "1") (pinfunction "1_1") (pintype "passive"))
      (node (ref "POWER-INPUT6") (pin "1") (pinfunction "1_1") (pintype "passive"))
      (node (ref "POWER-INPUT7") (pin "1") (pinfunction "1_1") (pintype "passive"))
      (node (ref "POWER-INPUT8") (pin "1") (pinfunction "1_1") (pintype "passive"))
      (node (ref "R11") (pin "P$1") (pinfunction "1_P$1") (pintype "passive"))
      (node (ref "R13") (pin "P$2") (pinfunction "2_P$2") (pintype "passive"))
      (node (ref "R49") (pin "P$1") (pinfunction "1_P$1") (pintype "passive"))
      (node (ref "R49") (pin "P$2") (pinfunction "2_P$2") (pintype "passive"))
      (node (ref "R51") (pin "P$2") (pinfunction "2_P$2") (pintype "passive"))
      (node (ref "U3") (pin "28") (pinfunction "PC5(ADC5/SCL)_28") (pintype "bidirectional"))
    )
    (net (code "11") (name "/D1-2") (class "Default")
      (node (ref "R65") (pin "P$1") (pinfunction "1_P$1") (pintype "passive"))
      (node (ref "U2") (pin "4") (pinfunction "PD2(INT0)_4") (pintype "bidirectional"))
      (node (ref "X7") (pin "1") (pinfunction "K_1") (pintype "passive"))
    )
    (net (code "12") (name "/D1-3") (class "Default")
      (node (ref "R36") (pin "P$1") (pinfunction "1_P$1") (pintype "passive"))
      (node (ref "U2") (pin "5") (pinfunction "PD3(INT1)_5") (pintype "bidirectional"))
      (node (ref "X7") (pin "2") (pinfunction "K_2") (pintype "passive"))
    )
    (net (code "13") (name "/D1-4") (class "Default")
      (node (ref "R35") (pin "P$1") (pinfunction "1_P$1") (pintype "passive"))
      (node (ref "U2") (pin "6") (pinfunction "PD4(XCK/T0)_6") (pintype "bidirectional"))
      (node (ref "X7") (pin "3") (pinfunction "K_3") (pintype "passive"))
    )
    (net (code "14") (name "/D1-6") (class "Default")
      (node (ref "R34") (pin "P$1") (pinfunction "1_P$1") (pintype "passive"))
      (node (ref "U2") (pin "12") (pinfunction "PD6(AIN0)_12") (pintype "bidirectional"))
      (node (ref "X7") (pin "4") (pinfunction "K_4") (pintype "passive"))
    )
    (net (code "15") (name "/D1-7") (class "Default")
      (node (ref "R69") (pin "P$1") (pinfunction "1_P$1") (pintype "passive"))
      (node (ref "U2") (pin "13") (pinfunction "PD7(AIN1)_13") (pintype "bidirectional"))
      (node (ref "X7") (pin "5") (pinfunction "K_5") (pintype "passive"))
    )
    (net (code "16") (name "/D1-8") (class "Default")
      (node (ref "R26") (pin "P$1") (pinfunction "1_P$1") (pintype "passive"))
      (node (ref "U2") (pin "14") (pinfunction "PB0(ICP)_14") (pintype "bidirectional"))
    )
    (net (code "17") (name "/D1-9") (class "Default")
      (node (ref "R24") (pin "P$1") (pinfunction "1_P$1") (pintype "passive"))
      (node (ref "U2") (pin "15") (pinfunction "PB1(OC1A)_15") (pintype "bidirectional"))
    )
    (net (code "18") (name "/D1-10") (class "Default")
      (node (ref "R22") (pin "P$1") (pinfunction "1_P$1") (pintype "passive"))
      (node (ref "U2") (pin "16") (pinfunction "PB2(SS/OC1B)_16") (pintype "bidirectional"))
    )
    (net (code "19") (name "/D1-11") (class "Default")
      (node (ref "R20") (pin "P$1") (pinfunction "1_P$1") (pintype "passive"))
      (node (ref "U2") (pin "17") (pinfunction "PB3(MOSI/OC2)_17") (pintype "bidirectional"))
    )
    (net (code "20") (name "/D1-12") (class "Default")
      (node (ref "R18") (pin "P$1") (pinfunction "1_P$1") (pintype "passive"))
      (node (ref "U2") (pin "18") (pinfunction "PB4(MISO)_18") (pintype "bidirectional"))
    )
    (net (code "21") (name "/D1-13") (class "Default")
      (node (ref "R16") (pin "P$1") (pinfunction "1_P$1") (pintype "passive"))
      (node (ref "U2") (pin "19") (pinfunction "PB5(SCK)_19") (pintype "bidirectional"))
    )
    (net (code "22") (name "/D3-0") (class "Default")
      (node (ref "R61") (pin "P$1") (pinfunction "1_P$1") (pintype "passive"))
      (node (ref "SV3") (pin "2") (pinfunction "2_2") (pintype "passive"))
      (node (ref "U3") (pin "2") (pinfunction "PD0(RXD)_2") (pintype "bidirectional"))
    )
    (net (code "23") (name "/D3-1") (class "Default")
      (node (ref "R60") (pin "P$1") (pinfunction "1_P$1") (pintype "passive"))
      (node (ref "SV3") (pin "4") (pinfunction "4_4") (pintype "passive"))
      (node (ref "U3") (pin "3") (pinfunction "PD1(TXD)_3") (pintype "bidirectional"))
    )
    (net (code "24") (name "/D3-2") (class "Default")
      (node (ref "R59") (pin "P$1") (pinfunction "1_P$1") (pintype "passive"))
      (node (ref "SV3") (pin "6") (pinfunction "6_6") (pintype "passive"))
      (node (ref "U3") (pin "4") (pinfunction "PD2(INT0)_4") (pintype "bidirectional"))
    )
    (net (code "25") (name "/D3-3") (class "Default")
      (node (ref "R58") (pin "P$1") (pinfunction "1_P$1") (pintype "passive"))
      (node (ref "SV3") (pin "8") (pinfunction "8_8") (pintype "passive"))
      (node (ref "U3") (pin "5") (pinfunction "PD3(INT1)_5") (pintype "bidirectional"))
    )
    (net (code "26") (name "/D3-4") (class "Default")
      (node (ref "R47") (pin "P$2") (pinfunction "2_P$2") (pintype "passive"))
      (node (ref "S8") (pin "1") (pinfunction "1_1") (pintype "passive"))
      (node (ref "U3") (pin "6") (pinfunction "PD4(XCK/T0)_6") (pintype "bidirectional"))
      (node (ref "X4") (pin "5") (pinfunction "K_5") (pintype "passive"))
    )
    (net (code "27") (name "/D3-5") (class "Default")
      (node (ref "R39") (pin "P$2") (pinfunction "2_P$2") (pintype "passive"))
      (node (ref "S7") (pin "1") (pinfunction "1_1") (pintype "passive"))
      (node (ref "U3") (pin "11") (pinfunction "PD5(T1)_11") (pintype "bidirectional"))
      (node (ref "X4") (pin "4") (pinfunction "K_4") (pintype "passive"))
    )
    (net (code "28") (name "/D3-6") (class "Default")
      (node (ref "S5") (pin "1") (pinfunction "1_1") (pintype "passive"))
      (node (ref "U3") (pin "12") (pinfunction "PD6(AIN0)_12") (pintype "bidirectional"))
      (node (ref "X4") (pin "3") (pinfunction "K_3") (pintype "passive"))
    )
    (net (code "29") (name "/D3-7") (class "Default")
      (node (ref "R44") (pin "P$2") (pinfunction "2_P$2") (pintype "passive"))
      (node (ref "U3") (pin "13") (pinfunction "PD7(AIN1)_13") (pintype "bidirectional"))
    )
    (net (code "30") (name "/D3-8") (class "Default")
      (node (ref "S2") (pin "1") (pinfunction "1_1") (pintype "passive"))
      (node (ref "U3") (pin "14") (pinfunction "PB0(ICP)_14") (pintype "bidirectional"))
      (node (ref "X4") (pin "1") (pinfunction "K_1") (pintype "passive"))
    )
    (net (code "31") (name "/D3-9") (class "Default")
      (node (ref "R75") (pin "P$1") (pinfunction "1_P$1") (pintype "passive"))
      (node (ref "U3") (pin "15") (pinfunction "PB1(OC1A)_15") (pintype "bidirectional"))
      (node (ref "X2") (pin "1") (pinfunction "K_1") (pintype "passive"))
    )
    (net (code "32") (name "/D3-10") (class "Default")
      (node (ref "R74") (pin "P$1") (pinfunction "1_P$1") (pintype "passive"))
      (node (ref "U3") (pin "16") (pinfunction "PB2(SS/OC1B)_16") (pintype "bidirectional"))
      (node (ref "X2") (pin "2") (pinfunction "K_2") (pintype "passive"))
    )
    (net (code "33") (name "/D3-11") (class "Default")
      (node (ref "R73") (pin "P$1") (pinfunction "1_P$1") (pintype "passive"))
      (node (ref "U3") (pin "17") (pinfunction "PB3(MOSI/OC2)_17") (pintype "bidirectional"))
      (node (ref "X2") (pin "3") (pinfunction "K_3") (pintype "passive"))
    )
    (net (code "34") (name "/D3-12") (class "Default")
      (node (ref "R63") (pin "P$1") (pinfunction "1_P$1") (pintype "passive"))
      (node (ref "U3") (pin "18") (pinfunction "PB4(MISO)_18") (pintype "bidirectional"))
      (node (ref "X2") (pin "4") (pinfunction "K_4") (pintype "passive"))
    )
    (net (code "35") (name "/D3-13") (class "Default")
      (node (ref "R76") (pin "P$1") (pinfunction "1_P$1") (pintype "passive"))
      (node (ref "U3") (pin "19") (pinfunction "PB5(SCK)_19") (pintype "bidirectional"))
      (node (ref "X2") (pin "5") (pinfunction "K_5") (pintype "passive"))
    )
    (net (code "36") (name "/N$71") (class "Default")
      (node (ref "R6") (pin "P$2") (pinfunction "2_P$2") (pintype "passive"))
    )
    (net (code "37") (name "/N$78") (class "Default")
      (node (ref "R45") (pin "P$2") (pinfunction "2_P$2") (pintype "passive"))
    )
    (net (code "38") (name "GND") (class "Default")
      (node (ref "7805") (pin "2") (pinfunction "GND_2") (pintype "power_in"))
      (node (ref "7808") (pin "2") (pinfunction "GND_2") (pintype "power_in"))
      (node (ref "C10") (pin "2") (pinfunction "2_2") (pintype "passive"))
      (node (ref "C5") (pin "1") (pinfunction "1_1") (pintype "passive"))
      (node (ref "C6") (pin "2") (pinfunction "2_2") (pintype "passive"))
      (node (ref "C7") (pin "2") (pinfunction "2_2") (pintype "passive"))
      (node (ref "C8") (pin "1") (pinfunction "1_1") (pintype "passive"))
      (node (ref "D2") (pin "A") (pinfunction "A_A") (pintype "passive"))
      (node (ref "D4") (pin "A") (pinfunction "A_A") (pintype "passive"))
      (node (ref "LED7") (pin "K") (pinfunction "C_K") (pintype "passive"))
      (node (ref "R10") (pin "P$1") (pinfunction "1_P$1") (pintype "passive"))
      (node (ref "R14") (pin "P$2") (pinfunction "2_P$2") (pintype "passive"))
      (node (ref "R27") (pin "P$1") (pinfunction "1_P$1") (pintype "passive"))
      (node (ref "R27") (pin "P$2") (pinfunction "2_P$2") (pintype "passive"))
      (node (ref "R28") (pin "P$1") (pinfunction "1_P$1") (pintype "passive"))
      (node (ref "R28") (pin "P$2") (pinfunction "2_P$2") (pintype "passive"))
      (node (ref "R29") (pin "P$2") (pinfunction "2_P$2") (pintype "passive"))
      (node (ref "R33") (pin "P$2") (pinfunction "2_P$2") (pintype "passive"))
      (node (ref "R34") (pin "P$2") (pinfunction "2_P$2") (pintype "passive"))
      (node (ref "R35") (pin "P$2") (pinfunction "2_P$2") (pintype "passive"))
      (node (ref "R37") (pin "P$1") (pinfunction "1_P$1") (pintype "passive"))
      (node (ref "R39") (pin "P$1") (pinfunction "1_P$1") (pintype "passive"))
      (node (ref "R40") (pin "P$1") (pinfunction "1_P$1") (pintype "passive"))
      (node (ref "R44") (pin "P$1") (pinfunction "1_P$1") (pintype "passive"))
      (node (ref "R45") (pin "P$1") (pinfunction "1_P$1") (pintype "passive"))
      (node (ref "R47") (pin "P$1") (pinfunction "1_P$1") (pintype "passive"))
      (node (ref "R52") (pin "P$2") (pinfunction "2_P$2") (pintype "passive"))
      (node (ref "R53") (pin "P$2") (pinfunction "2_P$2") (pintype "passive"))
      (node (ref "R54") (pin "P$2") (pinfunction "2_P$2") (pintype "passive"))
      (node (ref "R55") (pin "P$2") (pinfunction "2_P$2") (pintype "passive"))
      (node (ref "R57") (pin "P$1") (pinfunction "1_P$1") (pintype "passive"))
      (node (ref "R58") (pin "P$2") (pinfunction "2_P$2") (pintype "passive"))
      (node (ref "R59") (pin "P$2") (pinfunction "2_P$2") (pintype "passive"))
      (node (ref "R6") (pin "P$1") (pinfunction "1_P$1") (pintype "passive"))
      (node (ref "R60") (pin "P$2") (pinfunction "2_P$2") (pintype "passive"))
      (node (ref "R61") (pin "P$2") (pinfunction "2_P$2") (pintype "passive"))
      (node (ref "R63") (pin "P$2") (pinfunction "2_P$2") (pintype "passive"))
      (node (ref "R65") (pin "P$2") (pinfunction "2_P$2") (pintype "passive"))
      (node (ref "R66") (pin "P$2") (pinfunction "2_P$2") (pintype "passive"))
      (node (ref "R67") (pin "P$2") (pinfunction "2_P$2") (pintype "passive"))
      (node (ref "R68") (pin "P$2") (pinfunction "2_P$2") (pintype "passive"))
      (node (ref "R69") (pin "P$2") (pinfunction "2_P$2") (pintype "passive"))
      (node (ref "R70") (pin "P$1") (pinfunction "1_P$1") (pintype "passive"))
      (node (ref "R71") (pin "P$1") (pinfunction "1_P$1") (pintype "passive"))
      (node (ref "R73") (pin "P$2") (pinfunction "2_P$2") (pintype "passive"))
      (node (ref "R74") (pin "P$2") (pinfunction "2_P$2") (pintype "passive"))
      (node (ref "R75") (pin "P$2") (pinfunction "2_P$2") (pintype "passive"))
      (node (ref "R76") (pin "P$2") (pinfunction "2_P$2") (pintype "passive"))
      (node (ref "S1") (pin "4") (pinfunction "4_4") (pintype "passive"))
      (node (ref "S3") (pin "3") (pinfunction "3_3") (pintype "passive"))
      (node (ref "SV2") (pin "1") (pinfunction "1_1") (pintype "passive"))
      (node (ref "SV2") (pin "2") (pinfunction "2_2") (pintype "passive"))
      (node (ref "SV2") (pin "4") (pinfunction "4_4") (pintype "passive"))
      (node (ref "SV3") (pin "7") (pinfunction "7_7") (pintype "passive"))
      (node (ref "T12") (pin "1") (pinfunction "E_1") (pintype "passive"))
      (node (ref "T2") (pin "1") (pinfunction "E_1") (pintype "passive"))
      (node (ref "T4") (pin "1") (pinfunction "E_1") (pintype "passive"))
      (node (ref "T6") (pin "1") (pinfunction "E_1") (pintype "passive"))
      (node (ref "T8") (pin "1") (pinfunction "E_1") (pintype "passive"))
      (node (ref "X11") (pin "1") (pinfunction "K_1") (pintype "passive"))
      (node (ref "X11") (pin "2") (pinfunction "K_2") (pintype "passive"))
      (node (ref "X11") (pin "3") (pinfunction "K_3") (pintype "passive"))
      (node (ref "X11") (pin "4") (pinfunction "K_4") (pintype "passive"))
      (node (ref "X11") (pin "5") (pinfunction "K_5") (pintype "passive"))
      (node (ref "X11") (pin "6") (pinfunction "K_6") (pintype "passive"))
      (node (ref "X11") (pin "7") (pinfunction "K_7") (pintype "passive"))
      (node (ref "X11") (pin "8") (pinfunction "K_8") (pintype "passive"))
      (node (ref "X14") (pin "3") (pinfunction "K_3") (pintype "passive"))
    )
    (net (code "39") (name "Net-(7805-VIN)") (class "Default")
      (node (ref "7805") (pin "1") (pinfunction "VIN_1") (pintype "power_in"))
      (node (ref "7808") (pin "3") (pinfunction "VOUT_3") (pintype "power_in"))
      (node (ref "C10") (pin "1") (pinfunction "1_1") (pintype "passive"))
      (node (ref "C6") (pin "1") (pinfunction "1_1") (pintype "passive"))
    )
    (net (code "40") (name "Net-(7808-VIN)") (class "Default")
      (node (ref "7808") (pin "1") (pinfunction "VIN_1") (pintype "power_in"))
      (node (ref "C9") (pin "1") (pinfunction "1_1") (pintype "passive"))
      (node (ref "D1") (pin "C") (pinfunction "C_C") (pintype "passive"))
      (node (ref "D3") (pin "C") (pinfunction "C_C") (pintype "passive"))
      (node (ref "X14") (pin "1") (pinfunction "K_1") (pintype "passive"))
      (node (ref "X14") (pin "2") (pinfunction "K_2") (pintype "passive"))
    )
    (net (code "41") (name "Net-(D1-PadA)") (class "Default")
      (node (ref "D1") (pin "A") (pinfunction "A_A") (pintype "passive"))
      (node (ref "D2") (pin "C") (pinfunction "C_C") (pintype "passive"))
      (node (ref "POWER-INPUT") (pin "2") (pinfunction "2_2") (pintype "passive"))
    )
    (net (code "42") (name "Net-(D3-PadA)") (class "Default")
      (node (ref "D3") (pin "A") (pinfunction "A_A") (pintype "passive"))
      (node (ref "D4") (pin "C") (pinfunction "C_C") (pintype "passive"))
      (node (ref "POWER-INPUT") (pin "1") (pinfunction "1_1") (pintype "passive"))
    )
    (net (code "43") (name "Net-(LED1-C)") (class "Default")
      (node (ref "LED1") (pin "K") (pinfunction "C_K") (pintype "passive"))
      (node (ref "T2") (pin "3") (pinfunction "C_3") (pintype "passive"))
      (node (ref "U$1") (pin "COIL0") (pinfunction "COIL0_COIL0") (pintype "bidirectional"))
    )
    (net (code "44") (name "Net-(LED2-C)") (class "Default")
      (node (ref "LED2") (pin "K") (pinfunction "C_K") (pintype "passive"))
      (node (ref "T4") (pin "3") (pinfunction "C_3") (pintype "passive"))
      (node (ref "U$2") (pin "COIL0") (pinfunction "COIL0_COIL0") (pintype "bidirectional"))
    )
    (net (code "45") (name "Net-(LED3-C)") (class "Default")
      (node (ref "LED3") (pin "K") (pinfunction "C_K") (pintype "passive"))
      (node (ref "T6") (pin "3") (pinfunction "C_3") (pintype "passive"))
      (node (ref "U$3") (pin "COIL0") (pinfunction "COIL0_COIL0") (pintype "bidirectional"))
    )
    (net (code "46") (name "Net-(LED4-C)") (class "Default")
      (node (ref "LED4") (pin "K") (pinfunction "C_K") (pintype "passive"))
      (node (ref "T8") (pin "3") (pinfunction "C_3") (pintype "passive"))
      (node (ref "U$4") (pin "COIL0") (pinfunction "COIL0_COIL0") (pintype "bidirectional"))
    )
    (net (code "47") (name "Net-(LED5-C)") (class "Default")
      (node (ref "LED5") (pin "K") (pinfunction "C_K") (pintype "passive"))
      (node (ref "T10") (pin "3") (pinfunction "C_3") (pintype "passive"))
      (node (ref "U$5") (pin "COIL0") (pinfunction "COIL0_COIL0") (pintype "bidirectional"))
    )
    (net (code "48") (name "Net-(LED6-C)") (class "Default")
      (node (ref "LED6") (pin "K") (pinfunction "C_K") (pintype "passive"))
      (node (ref "T12") (pin "3") (pinfunction "C_3") (pintype "passive"))
      (node (ref "U$6") (pin "COIL0") (pinfunction "COIL0_COIL0") (pintype "bidirectional"))
    )
    (net (code "49") (name "Net-(R1-2)") (class "Default")
      (node (ref "R1") (pin "P$2") (pinfunction "2_P$2") (pintype "passive"))
      (node (ref "S1") (pin "1") (pinfunction "1_1") (pintype "passive"))
    )
    (net (code "50") (name "Net-(R2-1)") (class "Default")
      (node (ref "R2") (pin "P$1") (pinfunction "1_P$1") (pintype "passive"))
      (node (ref "R43") (pin "P$2") (pinfunction "2_P$2") (pintype "passive"))
    )
    (net (code "51") (name "Net-(R2-2)") (class "Default")
      (node (ref "R2") (pin "P$2") (pinfunction "2_P$2") (pintype "passive"))
      (node (ref "R3") (pin "P$1") (pinfunction "1_P$1") (pintype "passive"))
    )
    (net (code "52") (name "Net-(R3-2)") (class "Default")
      (node (ref "R3") (pin "P$2") (pinfunction "2_P$2") (pintype "passive"))
      (node (ref "R4") (pin "P$1") (pinfunction "1_P$1") (pintype "passive"))
    )
    (net (code "53") (name "Net-(R10-2)") (class "Default")
      (node (ref "R10") (pin "P$2") (pinfunction "2_P$2") (pintype "passive"))
      (node (ref "T10") (pin "1") (pinfunction "E_1") (pintype "passive"))
    )
    (net (code "54") (name "Net-(R11-2)") (class "Default")
      (node (ref "R11") (pin "P$2") (pinfunction "2_P$2") (pintype "passive"))
      (node (ref "R12") (pin "P$1") (pinfunction "1_P$1") (pintype "passive"))
    )
    (net (code "55") (name "Net-(R12-2)") (class "Default")
      (node (ref "R12") (pin "P$2") (pinfunction "2_P$2") (pintype "passive"))
      (node (ref "R13") (pin "P$1") (pinfunction "1_P$1") (pintype "passive"))
    )
    (net (code "56") (name "Net-(R14-1)") (class "Default")
      (node (ref "C1") (pin "1") (pinfunction "1_1") (pintype "passive"))
      (node (ref "C2") (pin "1") (pinfunction "1_1") (pintype "passive"))
      (node (ref "R14") (pin "P$1") (pinfunction "1_P$1") (pintype "passive"))
      (node (ref "R72") (pin "P$1") (pinfunction "1_P$1") (pintype "passive"))
    )
    (net (code "57") (name "Net-(R15-2)") (class "Default")
      (node (ref "LED1") (pin "A") (pinfunction "A_A") (pintype "passive"))
      (node (ref "R15") (pin "P$2") (pinfunction "2_P$2") (pintype "passive"))
    )
    (net (code "58") (name "Net-(R16-2)") (class "Default")
      (node (ref "R16") (pin "P$2") (pinfunction "2_P$2") (pintype "passive"))
      (node (ref "T2") (pin "2") (pinfunction "B_2") (pintype "passive"))
    )
    (net (code "59") (name "Net-(R17-1)") (class "Default")
      (node (ref "R17") (pin "P$1") (pinfunction "1_P$1") (pintype "passive"))
      (node (ref "R5") (pin "P$1") (pinfunction "1_P$1") (pintype "passive"))
      (node (ref "U$2") (pin "COIL1") (pinfunction "COIL1_COIL1") (pintype "bidirectional"))
    )
    (net (code "60") (name "Net-(R17-2)") (class "Default")
      (node (ref "LED2") (pin "A") (pinfunction "A_A") (pintype "passive"))
      (node (ref "R17") (pin "P$2") (pinfunction "2_P$2") (pintype "passive"))
    )
    (net (code "61") (name "Net-(R18-2)") (class "Default")
      (node (ref "R18") (pin "P$2") (pinfunction "2_P$2") (pintype "passive"))
      (node (ref "T4") (pin "2") (pinfunction "B_2") (pintype "passive"))
    )
    (net (code "62") (name "Net-(R19-2)") (class "Default")
      (node (ref "LED3") (pin "A") (pinfunction "A_A") (pintype "passive"))
      (node (ref "R19") (pin "P$2") (pinfunction "2_P$2") (pintype "passive"))
    )
    (net (code "63") (name "Net-(R20-2)") (class "Default")
      (node (ref "R20") (pin "P$2") (pinfunction "2_P$2") (pintype "passive"))
      (node (ref "T6") (pin "2") (pinfunction "B_2") (pintype "passive"))
    )
    (net (code "64") (name "Net-(R21-1)") (class "Default")
      (node (ref "R21") (pin "P$1") (pinfunction "1_P$1") (pintype "passive"))
      (node (ref "R31") (pin "P$1") (pinfunction "1_P$1") (pintype "passive"))
      (node (ref "U$4") (pin "COIL1") (pinfunction "COIL1_COIL1") (pintype "bidirectional"))
    )
    (net (code "65") (name "Net-(R21-2)") (class "Default")
      (node (ref "LED4") (pin "A") (pinfunction "A_A") (pintype "passive"))
      (node (ref "R21") (pin "P$2") (pinfunction "2_P$2") (pintype "passive"))
    )
    (net (code "66") (name "Net-(R22-2)") (class "Default")
      (node (ref "R22") (pin "P$2") (pinfunction "2_P$2") (pintype "passive"))
      (node (ref "T8") (pin "2") (pinfunction "B_2") (pintype "passive"))
    )
    (net (code "67") (name "Net-(R23-2)") (class "Default")
      (node (ref "LED5") (pin "A") (pinfunction "A_A") (pintype "passive"))
      (node (ref "R23") (pin "P$2") (pinfunction "2_P$2") (pintype "passive"))
    )
    (net (code "68") (name "Net-(R24-2)") (class "Default")
      (node (ref "R24") (pin "P$2") (pinfunction "2_P$2") (pintype "passive"))
      (node (ref "T10") (pin "2") (pinfunction "B_2") (pintype "passive"))
    )
    (net (code "69") (name "Net-(R25-2)") (class "Default")
      (node (ref "LED6") (pin "A") (pinfunction "A_A") (pintype "passive"))
      (node (ref "R25") (pin "P$2") (pinfunction "2_P$2") (pintype "passive"))
    )
    (net (code "70") (name "Net-(R26-2)") (class "Default")
      (node (ref "R26") (pin "P$2") (pinfunction "2_P$2") (pintype "passive"))
      (node (ref "T12") (pin "2") (pinfunction "B_2") (pintype "passive"))
    )
    (net (code "71") (name "Net-(R29-1)") (class "Default")
      (node (ref "C9") (pin "2") (pinfunction "2_2") (pintype "passive"))
      (node (ref "R29") (pin "P$1") (pinfunction "1_P$1") (pintype "passive"))
    )
    (net (code "72") (name "Net-(R30-1)") (class "Default")
      (node (ref "R30") (pin "P$1") (pinfunction "1_P$1") (pintype "passive"))
      (node (ref "SV2") (pin "11") (pinfunction "11_11") (pintype "passive"))
      (node (ref "SV2") (pin "3") (pinfunction "3_3") (pintype "passive"))
      (node (ref "SV2") (pin "5") (pinfunction "5_5") (pintype "passive"))
      (node (ref "SV2") (pin "7") (pinfunction "7_7") (pintype "passive"))
      (node (ref "SV2") (pin "9") (pinfunction "9_9") (pintype "passive"))
    )
    (net (code "73") (name "Net-(R36-2)") (class "Default")
      (node (ref "R36") (pin "P$2") (pinfunction "2_P$2") (pintype "passive"))
      (node (ref "R37") (pin "P$2") (pinfunction "2_P$2") (pintype "passive"))
    )
    (net (code "74") (name "Net-(R40-2)") (class "Default")
      (node (ref "R40") (pin "P$2") (pinfunction "2_P$2") (pintype "passive"))
      (node (ref "U3") (pin "22") (pinfunction "GND_22") (pintype "bidirectional"))
    )
    (net (code "75") (name "Net-(R41-2)") (class "Default")
      (node (ref "LED7") (pin "A") (pinfunction "A_A") (pintype "passive"))
      (node (ref "R41") (pin "P$2") (pinfunction "2_P$2") (pintype "passive"))
    )
    (net (code "76") (name "Net-(R42-2)") (class "Default")
      (node (ref "R42") (pin "P$2") (pinfunction "2_P$2") (pintype "passive"))
      (node (ref "S3") (pin "1") (pinfunction "1_1") (pintype "passive"))
    )
    (net (code "77") (name "Net-(R50-1)") (class "Default")
      (node (ref "R50") (pin "P$1") (pinfunction "1_P$1") (pintype "passive"))
      (node (ref "U2") (pin "27") (pinfunction "PC4(ADC4/SDA)_27") (pintype "bidirectional"))
    )
    (net (code "78") (name "Net-(R50-2)") (class "Default")
      (node (ref "R50") (pin "P$2") (pinfunction "2_P$2") (pintype "passive"))
      (node (ref "R8") (pin "P$2") (pinfunction "2_P$2") (pintype "passive"))
    )
    (net (code "79") (name "Net-(R51-1)") (class "Default")
      (node (ref "R51") (pin "P$1") (pinfunction "1_P$1") (pintype "passive"))
      (node (ref "U2") (pin "28") (pinfunction "PC5(ADC5/SCL)_28") (pintype "bidirectional"))
    )
    (net (code "80") (name "Net-(R56-1)") (class "Default")
      (node (ref "R56") (pin "P$1") (pinfunction "1_P$1") (pintype "passive"))
      (node (ref "R57") (pin "P$2") (pinfunction "2_P$2") (pintype "passive"))
    )
    (net (code "81") (name "Net-(R56-2)") (class "Default")
      (node (ref "R56") (pin "P$2") (pinfunction "2_P$2") (pintype "passive"))
      (node (ref "S1") (pin "3") (pinfunction "3_3") (pintype "passive"))
    )
    (net (code "82") (name "Net-(R64-1)") (class "Default")
      (node (ref "R64") (pin "P$1") (pinfunction "1_P$1") (pintype "passive"))
      (node (ref "U2") (pin "25") (pinfunction "PC2(ADC2)_25") (pintype "bidirectional"))
    )
    (net (code "83") (name "Net-(R70-2)") (class "Default")
      (node (ref "R70") (pin "P$2") (pinfunction "2_P$2") (pintype "passive"))
      (node (ref "U3") (pin "8") (pinfunction "GND_8") (pintype "bidirectional"))
    )
    (net (code "84") (name "Net-(R71-2)") (class "Default")
      (node (ref "R71") (pin "P$2") (pinfunction "2_P$2") (pintype "passive"))
      (node (ref "U2") (pin "22") (pinfunction "GND_22") (pintype "bidirectional"))
    )
    (net (code "85") (name "Net-(R72-2)") (class "Default")
      (node (ref "R72") (pin "P$2") (pinfunction "2_P$2") (pintype "passive"))
      (node (ref "U2") (pin "8") (pinfunction "GND_8") (pintype "bidirectional"))
    )
    (net (code "86") (name "Net-(T1-1)") (class "Default")
      (node (ref "T1") (pin "P$1") (pinfunction "1_P$1") (pintype "passive"))
      (node (ref "U$1") (pin "SWCLOSED") (pinfunction "SWCLOSE_SWCLOSED") (pintype "bidirectional"))
    )
    (net (code "87") (name "Net-(T1-2)") (class "Default")
      (node (ref "T1") (pin "P$2") (pinfunction "2_P$2") (pintype "passive"))
      (node (ref "U$1") (pin "SWCOMMON") (pinfunction "SWCOMMON_SWCOMMON") (pintype "bidirectional"))
    )
    (net (code "88") (name "Net-(T1-3)") (class "Default")
      (node (ref "T1") (pin "P$3") (pinfunction "3_P$3") (pintype "passive"))
      (node (ref "U$1") (pin "SWOPEN") (pinfunction "SWOPEN_SWOPEN") (pintype "bidirectional"))
    )
    (net (code "89") (name "Net-(T3-1)") (class "Default")
      (node (ref "T3") (pin "P$1") (pinfunction "1_P$1") (pintype "passive"))
      (node (ref "U$2") (pin "SWCLOSED") (pinfunction "SWCLOSE_SWCLOSED") (pintype "bidirectional"))
    )
    (net (code "90") (name "Net-(T3-2)") (class "Default")
      (node (ref "T3") (pin "P$2") (pinfunction "2_P$2") (pintype "passive"))
      (node (ref "U$2") (pin "SWCOMMON") (pinfunction "SWCOMMON_SWCOMMON") (pintype "bidirectional"))
    )
    (net (code "91") (name "Net-(T3-3)") (class "Default")
      (node (ref "T3") (pin "P$3") (pinfunction "3_P$3") (pintype "passive"))
      (node (ref "U$2") (pin "SWOPEN") (pinfunction "SWOPEN_SWOPEN") (pintype "bidirectional"))
    )
    (net (code "92") (name "Net-(T5-1)") (class "Default")
      (node (ref "T5") (pin "P$1") (pinfunction "1_P$1") (pintype "passive"))
      (node (ref "U$3") (pin "SWCLOSED") (pinfunction "SWCLOSE_SWCLOSED") (pintype "bidirectional"))
    )
    (net (code "93") (name "Net-(T5-2)") (class "Default")
      (node (ref "T5") (pin "P$2") (pinfunction "2_P$2") (pintype "passive"))
      (node (ref "U$3") (pin "SWCOMMON") (pinfunction "SWCOMMON_SWCOMMON") (pintype "bidirectional"))
    )
    (net (code "94") (name "Net-(T5-3)") (class "Default")
      (node (ref "T5") (pin "P$3") (pinfunction "3_P$3") (pintype "passive"))
      (node (ref "U$3") (pin "SWOPEN") (pinfunction "SWOPEN_SWOPEN") (pintype "bidirectional"))
    )
    (net (code "95") (name "Net-(T7-1)") (class "Default")
      (node (ref "T7") (pin "P$1") (pinfunction "1_P$1") (pintype "passive"))
      (node (ref "U$4") (pin "SWCLOSED") (pinfunction "SWCLOSE_SWCLOSED") (pintype "bidirectional"))
    )
    (net (code "96") (name "Net-(T7-2)") (class "Default")
      (node (ref "T7") (pin "P$2") (pinfunction "2_P$2") (pintype "passive"))
      (node (ref "U$4") (pin "SWCOMMON") (pinfunction "SWCOMMON_SWCOMMON") (pintype "bidirectional"))
    )
    (net (code "97") (name "Net-(T7-3)") (class "Default")
      (node (ref "T7") (pin "P$3") (pinfunction "3_P$3") (pintype "passive"))
      (node (ref "U$4") (pin "SWOPEN") (pinfunction "SWOPEN_SWOPEN") (pintype "bidirectional"))
    )
    (net (code "98") (name "Net-(T9-1)") (class "Default")
      (node (ref "T9") (pin "P$1") (pinfunction "1_P$1") (pintype "passive"))
      (node (ref "U$5") (pin "SWCLOSED") (pinfunction "SWCLOSE_SWCLOSED") (pintype "bidirectional"))
    )
    (net (code "99") (name "Net-(T9-2)") (class "Default")
      (node (ref "T9") (pin "P$2") (pinfunction "2_P$2") (pintype "passive"))
      (node (ref "U$5") (pin "SWCOMMON") (pinfunction "SWCOMMON_SWCOMMON") (pintype "bidirectional"))
    )
    (net (code "100") (name "Net-(T9-3)") (class "Default")
      (node (ref "T9") (pin "P$3") (pinfunction "3_P$3") (pintype "passive"))
      (node (ref "U$5") (pin "SWOPEN") (pinfunction "SWOPEN_SWOPEN") (pintype "bidirectional"))
    )
    (net (code "101") (name "Net-(T11-1)") (class "Default")
      (node (ref "T11") (pin "P$1") (pinfunction "1_P$1") (pintype "passive"))
      (node (ref "U$6") (pin "SWCLOSED") (pinfunction "SWCLOSE_SWCLOSED") (pintype "bidirectional"))
    )
    (net (code "102") (name "Net-(T11-2)") (class "Default")
      (node (ref "T11") (pin "P$2") (pinfunction "2_P$2") (pintype "passive"))
      (node (ref "U$6") (pin "SWCOMMON") (pinfunction "SWCOMMON_SWCOMMON") (pintype "bidirectional"))
    )
    (net (code "103") (name "Net-(T11-3)") (class "Default")
      (node (ref "T11") (pin "P$3") (pinfunction "3_P$3") (pintype "passive"))
      (node (ref "U$6") (pin "SWOPEN") (pinfunction "SWOPEN_SWOPEN") (pintype "bidirectional"))
    )
    (net (code "104") (name "Net-(U2-PB6(XTAL1{slash}TOSC1))") (class "Default")
      (node (ref "C2") (pin "2") (pinfunction "2_2") (pintype "passive"))
      (node (ref "U2") (pin "9") (pinfunction "PB6(XTAL1/TOSC1)_9") (pintype "bidirectional"))
      (node (ref "X1") (pin "2") (pinfunction "2_2") (pintype "passive"))
    )
    (net (code "105") (name "Net-(U2-PB7(XTAL2{slash}TOSC2))") (class "Default")
      (node (ref "C1") (pin "2") (pinfunction "2_2") (pintype "passive"))
      (node (ref "U2") (pin "10") (pinfunction "PB7(XTAL2/TOSC2)_10") (pintype "bidirectional"))
      (node (ref "X1") (pin "1") (pinfunction "1_1") (pintype "passive"))
    )
    (net (code "106") (name "Net-(U2-PC6({slash}RESET))") (class "Default")
      (node (ref "S1") (pin "2") (pinfunction "2_2") (pintype "passive"))
      (node (ref "U2") (pin "1") (pinfunction "PC6(/RESET)_1") (pintype "bidirectional"))
    )
    (net (code "107") (name "Net-(U3-PB6(XTAL1{slash}TOSC1))") (class "Default")
      (node (ref "C8") (pin "2") (pinfunction "2_2") (pintype "passive"))
      (node (ref "U3") (pin "9") (pinfunction "PB6(XTAL1/TOSC1)_9") (pintype "bidirectional"))
      (node (ref "X3") (pin "2") (pinfunction "2_2") (pintype "passive"))
    )
    (net (code "108") (name "Net-(U3-PB7(XTAL2{slash}TOSC2))") (class "Default")
      (node (ref "C5") (pin "2") (pinfunction "2_2") (pintype "passive"))
      (node (ref "U3") (pin "10") (pinfunction "PB7(XTAL2/TOSC2)_10") (pintype "bidirectional"))
      (node (ref "X3") (pin "1") (pinfunction "1_1") (pintype "passive"))
    )
    (net (code "109") (name "Net-(U3-PC6({slash}RESET))") (class "Default")
      (node (ref "S3") (pin "2") (pinfunction "2_2") (pintype "passive"))
      (node (ref "U3") (pin "1") (pinfunction "PC6(/RESET)_1") (pintype "bidirectional"))
    )
    (net (code "110") (name "Net-(X4B-K)") (class "Default")
      (node (ref "S4") (pin "1") (pinfunction "1_1") (pintype "passive"))
      (node (ref "X4") (pin "2") (pinfunction "K_2") (pintype "passive"))
    )
    (net (code "111") (name "VCC") (class "Default")
      (node (ref "7805") (pin "3") (pinfunction "VOUT_3") (pintype "power_in"))
      (node (ref "C7") (pin "1") (pinfunction "1_1") (pintype "passive"))
      (node (ref "R1") (pin "P$1") (pinfunction "1_P$1") (pintype "passive"))
      (node (ref "R15") (pin "P$1") (pinfunction "1_P$1") (pintype "passive"))
      (node (ref "R19") (pin "P$1") (pinfunction "1_P$1") (pintype "passive"))
      (node (ref "R23") (pin "P$1") (pinfunction "1_P$1") (pintype "passive"))
      (node (ref "R25") (pin "P$1") (pinfunction "1_P$1") (pintype "passive"))
      (node (ref "R30") (pin "P$2") (pinfunction "2_P$2") (pintype "passive"))
      (node (ref "R31") (pin "P$2") (pinfunction "2_P$2") (pintype "passive"))
      (node (ref "R41") (pin "P$1") (pinfunction "1_P$1") (pintype "passive"))
      (node (ref "R42") (pin "P$1") (pinfunction "1_P$1") (pintype "passive"))
      (node (ref "R5") (pin "P$2") (pinfunction "2_P$2") (pintype "passive"))
      (node (ref "R9") (pin "P$1") (pinfunction "1_P$1") (pintype "passive"))
      (node (ref "R9") (pin "P$2") (pinfunction "2_P$2") (pintype "passive"))
      (node (ref "S2") (pin "3") (pinfunction "3_3") (pintype "passive"))
      (node (ref "S4") (pin "3") (pinfunction "3_3") (pintype "passive"))
      (node (ref "S5") (pin "3") (pinfunction "3_3") (pintype "passive"))
      (node (ref "S7") (pin "3") (pinfunction "3_3") (pintype "passive"))
      (node (ref "S8") (pin "3") (pinfunction "3_3") (pintype "passive"))
      (node (ref "SV3") (pin "1") (pinfunction "1_1") (pintype "passive"))
      (node (ref "SV3") (pin "3") (pinfunction "3_3") (pintype "passive"))
      (node (ref "SV3") (pin "5") (pinfunction "5_5") (pintype "passive"))
      (node (ref "U$1") (pin "COIL1") (pinfunction "COIL1_COIL1") (pintype "bidirectional"))
      (node (ref "U$3") (pin "COIL1") (pinfunction "COIL1_COIL1") (pintype "bidirectional"))
      (node (ref "U$5") (pin "COIL1") (pinfunction "COIL1_COIL1") (pintype "bidirectional"))
      (node (ref "U$6") (pin "COIL1") (pinfunction "COIL1_COIL1") (pintype "bidirectional"))
      (node (ref "U2") (pin "20") (pinfunction "AVCC_20") (pintype "bidirectional"))
      (node (ref "U2") (pin "21") (pinfunction "AREF_21") (pintype "bidirectional"))
      (node (ref "U2") (pin "7") (pinfunction "VCC_7") (pintype "bidirectional"))
      (node (ref "U3") (pin "20") (pinfunction "AVCC_20") (pintype "bidirectional"))
      (node (ref "U3") (pin "21") (pinfunction "AREF_21") (pintype "bidirectional"))
      (node (ref "U3") (pin "7") (pinfunction "VCC_7") (pintype "bidirectional"))
      (node (ref "X10") (pin "1") (pinfunction "K_1") (pintype "passive"))
      (node (ref "X10") (pin "2") (pinfunction "K_2") (pintype "passive"))
      (node (ref "X10") (pin "3") (pinfunction "K_3") (pintype "passive"))
      (node (ref "X10") (pin "4") (pinfunction "K_4") (pintype "passive"))
      (node (ref "X10") (pin "5") (pinfunction "K_5") (pintype "passive"))
      (node (ref "X10") (pin "6") (pinfunction "K_6") (pintype "passive"))
      (node (ref "X10") (pin "7") (pinfunction "K_7") (pintype "passive"))
      (node (ref "X10") (pin "8") (pinfunction "K_8") (pintype "passive"))
    )
    (net (code "112") (name "unconnected-(S2-Pad2)") (class "Default")
      (node (ref "S2") (pin "2") (pinfunction "2_2") (pintype "passive"))
    )
    (net (code "113") (name "unconnected-(S2-Pad4)") (class "Default")
      (node (ref "S2") (pin "4") (pinfunction "4_4") (pintype "passive"))
    )
    (net (code "114") (name "unconnected-(S3-Pad4)") (class "Default")
      (node (ref "S3") (pin "4") (pinfunction "4_4") (pintype "passive"))
    )
    (net (code "115") (name "unconnected-(S4-Pad2)") (class "Default")
      (node (ref "S4") (pin "2") (pinfunction "2_2") (pintype "passive"))
    )
    (net (code "116") (name "unconnected-(S4-Pad4)") (class "Default")
      (node (ref "S4") (pin "4") (pinfunction "4_4") (pintype "passive"))
    )
    (net (code "117") (name "unconnected-(S5-Pad2)") (class "Default")
      (node (ref "S5") (pin "2") (pinfunction "2_2") (pintype "passive"))
    )
    (net (code "118") (name "unconnected-(S5-Pad4)") (class "Default")
      (node (ref "S5") (pin "4") (pinfunction "4_4") (pintype "passive"))
    )
    (net (code "119") (name "unconnected-(S7-Pad2)") (class "Default")
      (node (ref "S7") (pin "2") (pinfunction "2_2") (pintype "passive"))
    )
    (net (code "120") (name "unconnected-(S7-Pad4)") (class "Default")
      (node (ref "S7") (pin "4") (pinfunction "4_4") (pintype "passive"))
    )
    (net (code "121") (name "unconnected-(S8-Pad2)") (class "Default")
      (node (ref "S8") (pin "2") (pinfunction "2_2") (pintype "passive"))
    )
    (net (code "122") (name "unconnected-(S8-Pad4)") (class "Default")
      (node (ref "S8") (pin "4") (pinfunction "4_4") (pintype "passive"))
    )
    (net (code "123") (name "unconnected-(U2-PD0(RXD)-Pad2)") (class "Default")
      (node (ref "U2") (pin "2") (pinfunction "PD0(RXD)_2") (pintype "bidirectional"))
    )
    (net (code "124") (name "unconnected-(U2-PD1(TXD)-Pad3)") (class "Default")
      (node (ref "U2") (pin "3") (pinfunction "PD1(TXD)_3") (pintype "bidirectional"))
    )
    (net (code "125") (name "unconnected-(U2-PD5(T1)-Pad11)") (class "Default")
      (node (ref "U2") (pin "11") (pinfunction "PD5(T1)_11") (pintype "bidirectional"))
    )
    (net (code "126") (name "unconnected-(X6E-K-Pad5)") (class "Default")
      (node (ref "X6") (pin "5") (pinfunction "K_5") (pintype "passive"))
    )
  )
)
